# 50_Shot_Relay_V0_0.net
KiCad netlist of a schematic drawn in EAGLE
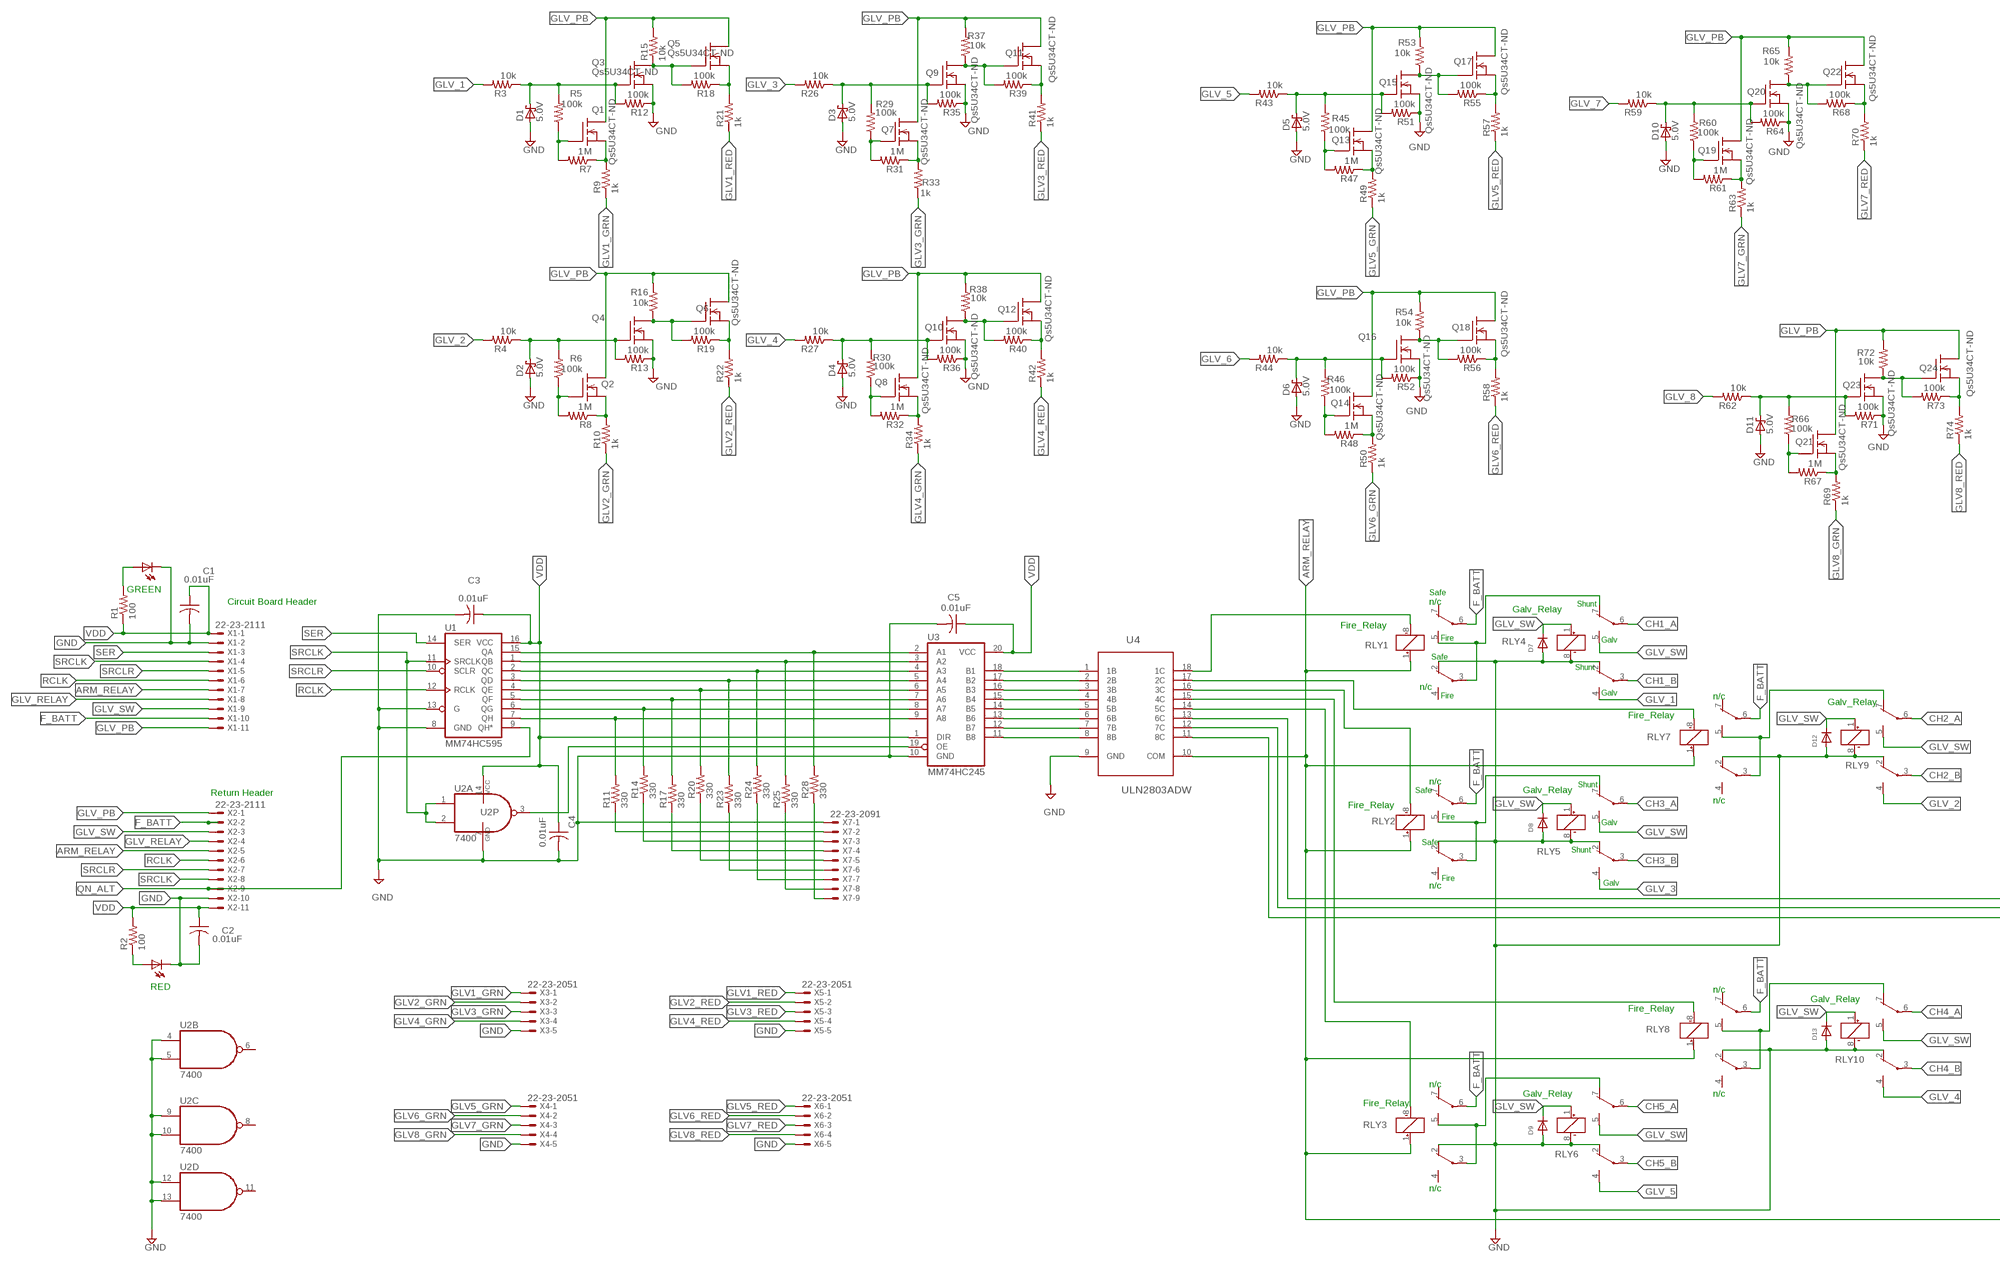
[diagram p0: schematic, sheet 1, part 1 of 2]
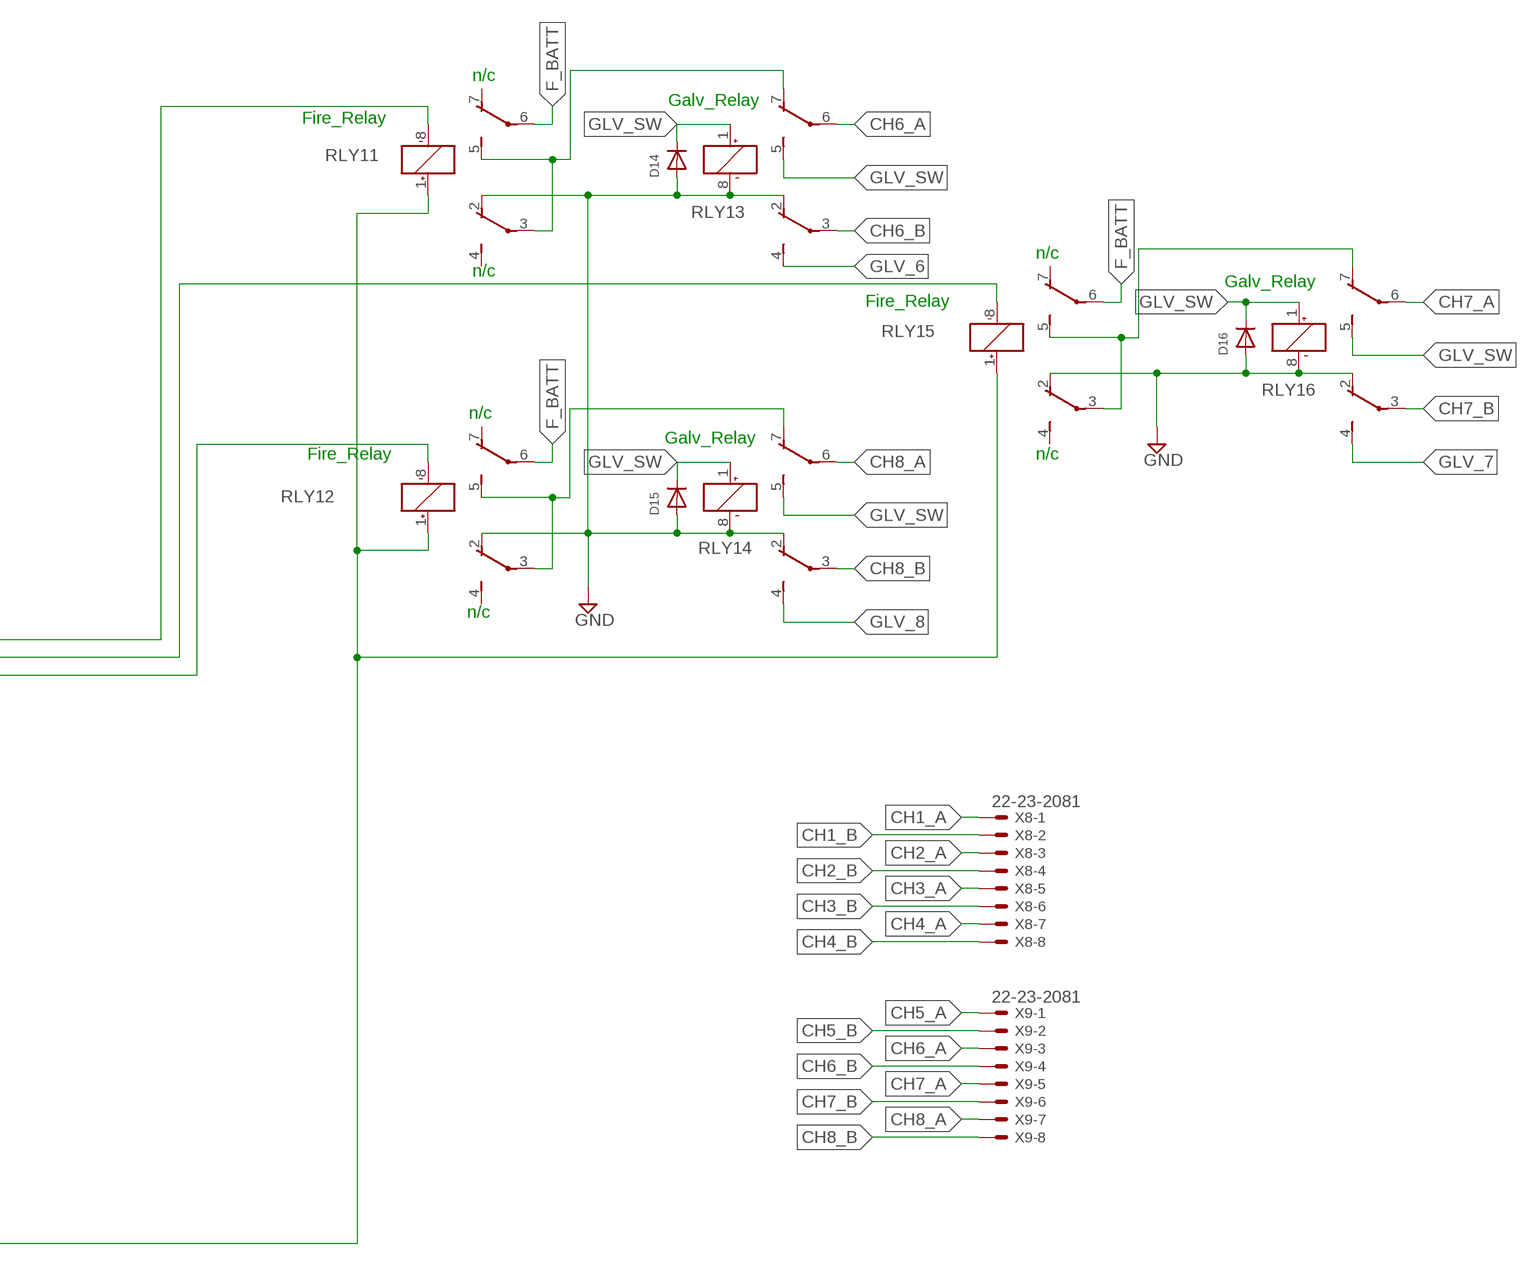
[diagram p1: schematic, sheet 1, part 2 of 2]

(export (version "E")
  (design (tool "Eeschema 10.0.6"))
  (components
    (comp (ref "C1")
      (value "0.01uF")
      (footprint "eagle-import:C0805")
      (fields (field (name "MPN") "VY2103M63Y5US63V7"))
      (libsource (lib "eagle-import") (part "C-USC0805"))
    )
    (comp (ref "C2")
      (value "0.01uF")
      (footprint "eagle-import:C0805")
      (fields (field (name "MPN") "VY2103M63Y5US63V7"))
      (libsource (lib "eagle-import") (part "C-USC0805"))
    )
    (comp (ref "C3")
      (value "0.01uF")
      (footprint "eagle-import:C0805")
      (libsource (lib "eagle-import") (part "C-USC0805"))
    )
    (comp (ref "C4")
      (value "0.01uF")
      (footprint "eagle-import:C0805")
      (libsource (lib "eagle-import") (part "C-USC0805"))
    )
    (comp (ref "C5")
      (value "0.01uF")
      (footprint "eagle-import:C0805")
      (libsource (lib "eagle-import") (part "C-USC0805"))
    )
    (comp (ref "D1")
      (value "5.0V")
      (footprint "eagle-import:SOT23")
      (libsource (lib "eagle-import") (part "568-6471-1-ND_ZENER_5.0V"))
    )
    (comp (ref "D2")
      (value "5.0V")
      (footprint "eagle-import:SOT23")
      (libsource (lib "eagle-import") (part "568-6471-1-ND_ZENER_5.0V"))
    )
    (comp (ref "D3")
      (value "5.0V")
      (footprint "eagle-import:SOT23")
      (libsource (lib "eagle-import") (part "568-6471-1-ND_ZENER_5.0V"))
    )
    (comp (ref "D4")
      (value "5.0V")
      (footprint "eagle-import:SOT23")
      (libsource (lib "eagle-import") (part "568-6471-1-ND_ZENER_5.0V"))
    )
    (comp (ref "D5")
      (value "5.0V")
      (footprint "eagle-import:SOT23")
      (libsource (lib "eagle-import") (part "568-6471-1-ND_ZENER_5.0V"))
    )
    (comp (ref "D6")
      (value "5.0V")
      (footprint "eagle-import:SOT23")
      (libsource (lib "eagle-import") (part "568-6471-1-ND_ZENER_5.0V"))
    )
    (comp (ref "D7")
      (value "SA2M-E3/5ATGICT-ND")
      (footprint "eagle-import:DO214AC")
      (libsource (lib "eagle-import") (part "DIODE_SA2M-E3/5ATGICT-ND"))
    )
    (comp (ref "D8")
      (value "SA2M-E3/5ATGICT-ND")
      (footprint "eagle-import:DO214AC")
      (libsource (lib "eagle-import") (part "DIODE_SA2M-E3/5ATGICT-ND"))
    )
    (comp (ref "D9")
      (value "SA2M-E3/5ATGICT-ND")
      (footprint "eagle-import:DO214AC")
      (libsource (lib "eagle-import") (part "DIODE_SA2M-E3/5ATGICT-ND"))
    )
    (comp (ref "D10")
      (value "5.0V")
      (footprint "eagle-import:SOT23")
      (libsource (lib "eagle-import") (part "568-6471-1-ND_ZENER_5.0V"))
    )
    (comp (ref "D11")
      (value "5.0V")
      (footprint "eagle-import:SOT23")
      (libsource (lib "eagle-import") (part "568-6471-1-ND_ZENER_5.0V"))
    )
    (comp (ref "D12")
      (value "SA2M-E3/5ATGICT-ND")
      (footprint "eagle-import:DO214AC")
      (libsource (lib "eagle-import") (part "DIODE_SA2M-E3/5ATGICT-ND"))
    )
    (comp (ref "D13")
      (value "SA2M-E3/5ATGICT-ND")
      (footprint "eagle-import:DO214AC")
      (libsource (lib "eagle-import") (part "DIODE_SA2M-E3/5ATGICT-ND"))
    )
    (comp (ref "D14")
      (value "SA2M-E3/5ATGICT-ND")
      (footprint "eagle-import:DO214AC")
      (libsource (lib "eagle-import") (part "DIODE_SA2M-E3/5ATGICT-ND"))
    )
    (comp (ref "D15")
      (value "SA2M-E3/5ATGICT-ND")
      (footprint "eagle-import:DO214AC")
      (libsource (lib "eagle-import") (part "DIODE_SA2M-E3/5ATGICT-ND"))
    )
    (comp (ref "D16")
      (value "SA2M-E3/5ATGICT-ND")
      (footprint "eagle-import:DO214AC")
      (libsource (lib "eagle-import") (part "DIODE_SA2M-E3/5ATGICT-ND"))
    )
    (comp (ref "LED1")
      (value "LEDCHIP-LED0805")
      (footprint "eagle-import:CHIP-LED0805")
      (libsource (lib "eagle-import") (part "LEDCHIP-LED0805"))
    )
    (comp (ref "LED2")
      (value "LEDCHIP-LED0805")
      (footprint "eagle-import:CHIP-LED0805")
      (libsource (lib "eagle-import") (part "LEDCHIP-LED0805"))
    )
    (comp (ref "Q1")
      (value "Qs5U34CT-ND")
      (footprint "eagle-import:SOT23-5L")
      (libsource (lib "eagle-import") (part "QS5U34CT-ND_MOSFET_N_CHANNEL"))
    )
    (comp (ref "Q2")
      (value "Qs5U34CT-ND")
      (footprint "eagle-import:SOT23-5L")
      (libsource (lib "eagle-import") (part "QS5U34CT-ND_MOSFET_N_CHANNEL"))
    )
    (comp (ref "Q3")
      (value "Qs5U34CT-ND")
      (footprint "eagle-import:SOT23-5L")
      (libsource (lib "eagle-import") (part "QS5U34CT-ND_MOSFET_N_CHANNEL"))
    )
    (comp (ref "Q4")
      (value "Qs5U34CT-ND")
      (footprint "eagle-import:SOT23-5L")
      (libsource (lib "eagle-import") (part "QS5U34CT-ND_MOSFET_N_CHANNEL"))
    )
    (comp (ref "Q5")
      (value "Qs5U34CT-ND")
      (footprint "eagle-import:SOT23-5L")
      (libsource (lib "eagle-import") (part "QS5U34CT-ND_MOSFET_N_CHANNEL"))
    )
    (comp (ref "Q6")
      (value "Qs5U34CT-ND")
      (footprint "eagle-import:SOT23-5L")
      (libsource (lib "eagle-import") (part "QS5U34CT-ND_MOSFET_N_CHANNEL"))
    )
    (comp (ref "Q7")
      (value "Qs5U34CT-ND")
      (footprint "eagle-import:SOT23-5L")
      (libsource (lib "eagle-import") (part "QS5U34CT-ND_MOSFET_N_CHANNEL"))
    )
    (comp (ref "Q8")
      (value "Qs5U34CT-ND")
      (footprint "eagle-import:SOT23-5L")
      (libsource (lib "eagle-import") (part "QS5U34CT-ND_MOSFET_N_CHANNEL"))
    )
    (comp (ref "Q9")
      (value "Qs5U34CT-ND")
      (footprint "eagle-import:SOT23-5L")
      (libsource (lib "eagle-import") (part "QS5U34CT-ND_MOSFET_N_CHANNEL"))
    )
    (comp (ref "Q10")
      (value "Qs5U34CT-ND")
      (footprint "eagle-import:SOT23-5L")
      (libsource (lib "eagle-import") (part "QS5U34CT-ND_MOSFET_N_CHANNEL"))
    )
    (comp (ref "Q11")
      (value "Qs5U34CT-ND")
      (footprint "eagle-import:SOT23-5L")
      (libsource (lib "eagle-import") (part "QS5U34CT-ND_MOSFET_N_CHANNEL"))
    )
    (comp (ref "Q12")
      (value "Qs5U34CT-ND")
      (footprint "eagle-import:SOT23-5L")
      (libsource (lib "eagle-import") (part "QS5U34CT-ND_MOSFET_N_CHANNEL"))
    )
    (comp (ref "Q13")
      (value "Qs5U34CT-ND")
      (footprint "eagle-import:SOT23-5L")
      (libsource (lib "eagle-import") (part "QS5U34CT-ND_MOSFET_N_CHANNEL"))
    )
    (comp (ref "Q14")
      (value "Qs5U34CT-ND")
      (footprint "eagle-import:SOT23-5L")
      (libsource (lib "eagle-import") (part "QS5U34CT-ND_MOSFET_N_CHANNEL"))
    )
    (comp (ref "Q15")
      (value "Qs5U34CT-ND")
      (footprint "eagle-import:SOT23-5L")
      (libsource (lib "eagle-import") (part "QS5U34CT-ND_MOSFET_N_CHANNEL"))
    )
    (comp (ref "Q16")
      (value "Qs5U34CT-ND")
      (footprint "eagle-import:SOT23-5L")
      (libsource (lib "eagle-import") (part "QS5U34CT-ND_MOSFET_N_CHANNEL"))
    )
    (comp (ref "Q17")
      (value "Qs5U34CT-ND")
      (footprint "eagle-import:SOT23-5L")
      (libsource (lib "eagle-import") (part "QS5U34CT-ND_MOSFET_N_CHANNEL"))
    )
    (comp (ref "Q18")
      (value "Qs5U34CT-ND")
      (footprint "eagle-import:SOT23-5L")
      (libsource (lib "eagle-import") (part "QS5U34CT-ND_MOSFET_N_CHANNEL"))
    )
    (comp (ref "Q19")
      (value "Qs5U34CT-ND")
      (footprint "eagle-import:SOT23-5L")
      (libsource (lib "eagle-import") (part "QS5U34CT-ND_MOSFET_N_CHANNEL"))
    )
    (comp (ref "Q20")
      (value "Qs5U34CT-ND")
      (footprint "eagle-import:SOT23-5L")
      (libsource (lib "eagle-import") (part "QS5U34CT-ND_MOSFET_N_CHANNEL"))
    )
    (comp (ref "Q21")
      (value "Qs5U34CT-ND")
      (footprint "eagle-import:SOT23-5L")
      (libsource (lib "eagle-import") (part "QS5U34CT-ND_MOSFET_N_CHANNEL"))
    )
    (comp (ref "Q22")
      (value "Qs5U34CT-ND")
      (footprint "eagle-import:SOT23-5L")
      (libsource (lib "eagle-import") (part "QS5U34CT-ND_MOSFET_N_CHANNEL"))
    )
    (comp (ref "Q23")
      (value "Qs5U34CT-ND")
      (footprint "eagle-import:SOT23-5L")
      (libsource (lib "eagle-import") (part "QS5U34CT-ND_MOSFET_N_CHANNEL"))
    )
    (comp (ref "Q24")
      (value "Qs5U34CT-ND")
      (footprint "eagle-import:SOT23-5L")
      (libsource (lib "eagle-import") (part "QS5U34CT-ND_MOSFET_N_CHANNEL"))
    )
    (comp (ref "R1")
      (value "100")
      (footprint "eagle-import:M0805")
      (libsource (lib "eagle-import") (part "R-US_M0805"))
    )
    (comp (ref "R2")
      (value "100")
      (footprint "eagle-import:M0805")
      (libsource (lib "eagle-import") (part "R-US_M0805"))
    )
    (comp (ref "R3")
      (value "10k")
      (footprint "eagle-import:M0805")
      (libsource (lib "eagle-import") (part "R-US_M0805"))
    )
    (comp (ref "R4")
      (value "10k")
      (footprint "eagle-import:M0805")
      (libsource (lib "eagle-import") (part "R-US_M0805"))
    )
    (comp (ref "R5")
      (value "100k")
      (footprint "eagle-import:M0805")
      (libsource (lib "eagle-import") (part "R-US_M0805"))
    )
    (comp (ref "R6")
      (value "100k")
      (footprint "eagle-import:M0805")
      (libsource (lib "eagle-import") (part "R-US_M0805"))
    )
    (comp (ref "R7")
      (value "1M")
      (footprint "eagle-import:M0805")
      (libsource (lib "eagle-import") (part "R-US_M0805"))
    )
    (comp (ref "R8")
      (value "1M")
      (footprint "eagle-import:M0805")
      (libsource (lib "eagle-import") (part "R-US_M0805"))
    )
    (comp (ref "R9")
      (value "1k")
      (footprint "eagle-import:M0805")
      (libsource (lib "eagle-import") (part "R-US_M0805"))
    )
    (comp (ref "R10")
      (value "1k")
      (footprint "eagle-import:M0805")
      (libsource (lib "eagle-import") (part "R-US_M0805"))
    )
    (comp (ref "R11")
      (value "330")
      (footprint "eagle-import:M0805")
      (libsource (lib "eagle-import") (part "R-US_M0805"))
    )
    (comp (ref "R12")
      (value "100k")
      (footprint "eagle-import:M0805")
      (libsource (lib "eagle-import") (part "R-US_M0805"))
    )
    (comp (ref "R13")
      (value "100k")
      (footprint "eagle-import:M0805")
      (libsource (lib "eagle-import") (part "R-US_M0805"))
    )
    (comp (ref "R14")
      (value "330")
      (footprint "eagle-import:M0805")
      (libsource (lib "eagle-import") (part "R-US_M0805"))
    )
    (comp (ref "R15")
      (value "10k")
      (footprint "eagle-import:M0805")
      (libsource (lib "eagle-import") (part "R-US_M0805"))
    )
    (comp (ref "R16")
      (value "10k")
      (footprint "eagle-import:M0805")
      (libsource (lib "eagle-import") (part "R-US_M0805"))
    )
    (comp (ref "R17")
      (value "330")
      (footprint "eagle-import:M0805")
      (libsource (lib "eagle-import") (part "R-US_M0805"))
    )
    (comp (ref "R18")
      (value "100k")
      (footprint "eagle-import:M0805")
      (libsource (lib "eagle-import") (part "R-US_M0805"))
    )
    (comp (ref "R19")
      (value "100k")
      (footprint "eagle-import:M0805")
      (libsource (lib "eagle-import") (part "R-US_M0805"))
    )
    (comp (ref "R20")
      (value "330")
      (footprint "eagle-import:M0805")
      (libsource (lib "eagle-import") (part "R-US_M0805"))
    )
    (comp (ref "R21")
      (value "1k")
      (footprint "eagle-import:M0805")
      (libsource (lib "eagle-import") (part "R-US_M0805"))
    )
    (comp (ref "R22")
      (value "1k")
      (footprint "eagle-import:M0805")
      (libsource (lib "eagle-import") (part "R-US_M0805"))
    )
    (comp (ref "R23")
      (value "330")
      (footprint "eagle-import:M0805")
      (libsource (lib "eagle-import") (part "R-US_M0805"))
    )
    (comp (ref "R24")
      (value "330")
      (footprint "eagle-import:M0805")
      (libsource (lib "eagle-import") (part "R-US_M0805"))
    )
    (comp (ref "R25")
      (value "330")
      (footprint "eagle-import:M0805")
      (libsource (lib "eagle-import") (part "R-US_M0805"))
    )
    (comp (ref "R26")
      (value "10k")
      (footprint "eagle-import:M0805")
      (libsource (lib "eagle-import") (part "R-US_M0805"))
    )
    (comp (ref "R27")
      (value "10k")
      (footprint "eagle-import:M0805")
      (libsource (lib "eagle-import") (part "R-US_M0805"))
    )
    (comp (ref "R28")
      (value "330")
      (footprint "eagle-import:M0805")
      (libsource (lib "eagle-import") (part "R-US_M0805"))
    )
    (comp (ref "R29")
      (value "100k")
      (footprint "eagle-import:M0805")
      (libsource (lib "eagle-import") (part "R-US_M0805"))
    )
    (comp (ref "R30")
      (value "100k")
      (footprint "eagle-import:M0805")
      (libsource (lib "eagle-import") (part "R-US_M0805"))
    )
    (comp (ref "R31")
      (value "1M")
      (footprint "eagle-import:M0805")
      (libsource (lib "eagle-import") (part "R-US_M0805"))
    )
    (comp (ref "R32")
      (value "1M")
      (footprint "eagle-import:M0805")
      (libsource (lib "eagle-import") (part "R-US_M0805"))
    )
    (comp (ref "R33")
      (value "1k")
      (footprint "eagle-import:M0805")
      (libsource (lib "eagle-import") (part "R-US_M0805"))
    )
    (comp (ref "R34")
      (value "1k")
      (footprint "eagle-import:M0805")
      (libsource (lib "eagle-import") (part "R-US_M0805"))
    )
    (comp (ref "R35")
      (value "100k")
      (footprint "eagle-import:M0805")
      (libsource (lib "eagle-import") (part "R-US_M0805"))
    )
    (comp (ref "R36")
      (value "100k")
      (footprint "eagle-import:M0805")
      (libsource (lib "eagle-import") (part "R-US_M0805"))
    )
    (comp (ref "R37")
      (value "10k")
      (footprint "eagle-import:M0805")
      (libsource (lib "eagle-import") (part "R-US_M0805"))
    )
    (comp (ref "R38")
      (value "10k")
      (footprint "eagle-import:M0805")
      (libsource (lib "eagle-import") (part "R-US_M0805"))
    )
    (comp (ref "R39")
      (value "100k")
      (footprint "eagle-import:M0805")
      (libsource (lib "eagle-import") (part "R-US_M0805"))
    )
    (comp (ref "R40")
      (value "100k")
      (footprint "eagle-import:M0805")
      (libsource (lib "eagle-import") (part "R-US_M0805"))
    )
    (comp (ref "R41")
      (value "1k")
      (footprint "eagle-import:M0805")
      (libsource (lib "eagle-import") (part "R-US_M0805"))
    )
    (comp (ref "R42")
      (value "1k")
      (footprint "eagle-import:M0805")
      (libsource (lib "eagle-import") (part "R-US_M0805"))
    )
    (comp (ref "R43")
      (value "10k")
      (footprint "eagle-import:M0805")
      (libsource (lib "eagle-import") (part "R-US_M0805"))
    )
    (comp (ref "R44")
      (value "10k")
      (footprint "eagle-import:M0805")
      (libsource (lib "eagle-import") (part "R-US_M0805"))
    )
    (comp (ref "R45")
      (value "100k")
      (footprint "eagle-import:M0805")
      (libsource (lib "eagle-import") (part "R-US_M0805"))
    )
    (comp (ref "R46")
      (value "100k")
      (footprint "eagle-import:M0805")
      (libsource (lib "eagle-import") (part "R-US_M0805"))
    )
    (comp (ref "R47")
      (value "1M")
      (footprint "eagle-import:M0805")
      (libsource (lib "eagle-import") (part "R-US_M0805"))
    )
    (comp (ref "R48")
      (value "1M")
      (footprint "eagle-import:M0805")
      (libsource (lib "eagle-import") (part "R-US_M0805"))
    )
    (comp (ref "R49")
      (value "1k")
      (footprint "eagle-import:M0805")
      (libsource (lib "eagle-import") (part "R-US_M0805"))
    )
    (comp (ref "R50")
      (value "1k")
      (footprint "eagle-import:M0805")
      (libsource (lib "eagle-import") (part "R-US_M0805"))
    )
    (comp (ref "R51")
      (value "100k")
      (footprint "eagle-import:M0805")
      (libsource (lib "eagle-import") (part "R-US_M0805"))
    )
    (comp (ref "R52")
      (value "100k")
      (footprint "eagle-import:M0805")
      (libsource (lib "eagle-import") (part "R-US_M0805"))
    )
    (comp (ref "R53")
      (value "10k")
      (footprint "eagle-import:M0805")
      (libsource (lib "eagle-import") (part "R-US_M0805"))
    )
    (comp (ref "R54")
      (value "10k")
      (footprint "eagle-import:M0805")
      (libsource (lib "eagle-import") (part "R-US_M0805"))
    )
    (comp (ref "R55")
      (value "100k")
      (footprint "eagle-import:M0805")
      (libsource (lib "eagle-import") (part "R-US_M0805"))
    )
    (comp (ref "R56")
      (value "100k")
      (footprint "eagle-import:M0805")
      (libsource (lib "eagle-import") (part "R-US_M0805"))
    )
    (comp (ref "R57")
      (value "1k")
      (footprint "eagle-import:M0805")
      (libsource (lib "eagle-import") (part "R-US_M0805"))
    )
    (comp (ref "R58")
      (value "1k")
      (footprint "eagle-import:M0805")
      (libsource (lib "eagle-import") (part "R-US_M0805"))
    )
    (comp (ref "R59")
      (value "10k")
      (footprint "eagle-import:M0805")
      (libsource (lib "eagle-import") (part "R-US_M0805"))
    )
    (comp (ref "R60")
      (value "100k")
      (footprint "eagle-import:M0805")
      (libsource (lib "eagle-import") (part "R-US_M0805"))
    )
    (comp (ref "R61")
      (value "1M")
      (footprint "eagle-import:M0805")
      (libsource (lib "eagle-import") (part "R-US_M0805"))
    )
    (comp (ref "R62")
      (value "10k")
      (footprint "eagle-import:M0805")
      (libsource (lib "eagle-import") (part "R-US_M0805"))
    )
    (comp (ref "R63")
      (value "1k")
      (footprint "eagle-import:M0805")
      (libsource (lib "eagle-import") (part "R-US_M0805"))
    )
    (comp (ref "R64")
      (value "100k")
      (footprint "eagle-import:M0805")
      (libsource (lib "eagle-import") (part "R-US_M0805"))
    )
    (comp (ref "R65")
      (value "10k")
      (footprint "eagle-import:M0805")
      (libsource (lib "eagle-import") (part "R-US_M0805"))
    )
    (comp (ref "R66")
      (value "100k")
      (footprint "eagle-import:M0805")
      (libsource (lib "eagle-import") (part "R-US_M0805"))
    )
    (comp (ref "R67")
      (value "1M")
      (footprint "eagle-import:M0805")
      (libsource (lib "eagle-import") (part "R-US_M0805"))
    )
    (comp (ref "R68")
      (value "100k")
      (footprint "eagle-import:M0805")
      (libsource (lib "eagle-import") (part "R-US_M0805"))
    )
    (comp (ref "R69")
      (value "1k")
      (footprint "eagle-import:M0805")
      (libsource (lib "eagle-import") (part "R-US_M0805"))
    )
    (comp (ref "R70")
      (value "1k")
      (footprint "eagle-import:M0805")
      (libsource (lib "eagle-import") (part "R-US_M0805"))
    )
    (comp (ref "R71")
      (value "100k")
      (footprint "eagle-import:M0805")
      (libsource (lib "eagle-import") (part "R-US_M0805"))
    )
    (comp (ref "R72")
      (value "10k")
      (footprint "eagle-import:M0805")
      (libsource (lib "eagle-import") (part "R-US_M0805"))
    )
    (comp (ref "R73")
      (value "100k")
      (footprint "eagle-import:M0805")
      (libsource (lib "eagle-import") (part "R-US_M0805"))
    )
    (comp (ref "R74")
      (value "1k")
      (footprint "eagle-import:M0805")
      (libsource (lib "eagle-import") (part "R-US_M0805"))
    )
    (comp (ref "RLY1")
      (value "OMRON")
      (footprint "eagle-import:OMRONG6S")
      (fields (field (name "OC_NEWARK") "unknown"))
      (libsource (lib "eagle-import") (part "OMRON"))
    )
    (comp (ref "RLY2")
      (value "OMRON")
      (footprint "eagle-import:OMRONG6S")
      (fields (field (name "OC_NEWARK") "unknown"))
      (libsource (lib "eagle-import") (part "OMRON"))
    )
    (comp (ref "RLY3")
      (value "OMRON")
      (footprint "eagle-import:OMRONG6S")
      (fields (field (name "OC_NEWARK") "unknown"))
      (libsource (lib "eagle-import") (part "OMRON"))
    )
    (comp (ref "RLY4")
      (value "OMRON")
      (footprint "eagle-import:OMRONG6S")
      (fields (field (name "OC_NEWARK") "unknown"))
      (libsource (lib "eagle-import") (part "OMRON"))
    )
    (comp (ref "RLY5")
      (value "OMRON")
      (footprint "eagle-import:OMRONG6S")
      (fields (field (name "OC_NEWARK") "unknown"))
      (libsource (lib "eagle-import") (part "OMRON"))
    )
    (comp (ref "RLY6")
      (value "OMRON")
      (footprint "eagle-import:OMRONG6S")
      (fields (field (name "OC_NEWARK") "unknown"))
      (libsource (lib "eagle-import") (part "OMRON"))
    )
    (comp (ref "RLY7")
      (value "OMRON")
      (footprint "eagle-import:OMRONG6S")
      (fields (field (name "OC_NEWARK") "unknown"))
      (libsource (lib "eagle-import") (part "OMRON"))
    )
    (comp (ref "RLY8")
      (value "OMRON")
      (footprint "eagle-import:OMRONG6S")
      (fields (field (name "OC_NEWARK") "unknown"))
      (libsource (lib "eagle-import") (part "OMRON"))
    )
    (comp (ref "RLY9")
      (value "OMRON")
      (footprint "eagle-import:OMRONG6S")
      (fields (field (name "OC_NEWARK") "unknown"))
      (libsource (lib "eagle-import") (part "OMRON"))
    )
    (comp (ref "RLY10")
      (value "OMRON")
      (footprint "eagle-import:OMRONG6S")
      (fields (field (name "OC_NEWARK") "unknown"))
      (libsource (lib "eagle-import") (part "OMRON"))
    )
    (comp (ref "RLY11")
      (value "OMRON")
      (footprint "eagle-import:OMRONG6S")
      (fields (field (name "OC_NEWARK") "unknown"))
      (libsource (lib "eagle-import") (part "OMRON"))
    )
    (comp (ref "RLY12")
      (value "OMRON")
      (footprint "eagle-import:OMRONG6S")
      (fields (field (name "OC_NEWARK") "unknown"))
      (libsource (lib "eagle-import") (part "OMRON"))
    )
    (comp (ref "RLY13")
      (value "OMRON")
      (footprint "eagle-import:OMRONG6S")
      (fields (field (name "OC_NEWARK") "unknown"))
      (libsource (lib "eagle-import") (part "OMRON"))
    )
    (comp (ref "RLY14")
      (value "OMRON")
      (footprint "eagle-import:OMRONG6S")
      (fields (field (name "OC_NEWARK") "unknown"))
      (libsource (lib "eagle-import") (part "OMRON"))
    )
    (comp (ref "RLY15")
      (value "OMRON")
      (footprint "eagle-import:OMRONG6S")
      (fields (field (name "OC_NEWARK") "unknown"))
      (libsource (lib "eagle-import") (part "OMRON"))
    )
    (comp (ref "RLY16")
      (value "OMRON")
      (footprint "eagle-import:OMRONG6S")
      (fields (field (name "OC_NEWARK") "unknown"))
      (libsource (lib "eagle-import") (part "OMRON"))
    )
    (comp (ref "U1")
      (value "MM74HC595")
      (footprint "eagle-import:TSSOP16")
      (libsource (lib "eagle-import") (part "MM74HC595"))
    )
    (comp (ref "U2")
      (value "7400")
      (footprint "eagle-import:TSSOP14")
      (fields (field (name "OC_NEWARK") "unknown"))
      (libsource (lib "eagle-import") (part "7400"))
    )
    (comp (ref "U3")
      (value "MM74HC245")
      (footprint "eagle-import:TSSOP20")
      (libsource (lib "eagle-import") (part "MM74HC245"))
    )
    (comp (ref "U4")
      (value "ULN2803ADW")
      (footprint "eagle-import:SOIC127P1030X265-18N")
      (fields (field (name "MF") "TEXAS INSTRUMENTS"))
      (libsource (lib "eagle-import") (part "ULN2803ADW"))
    )
    (comp (ref "X1")
      (value "22-23-2111")
      (footprint "eagle-import:22-23-2111")
      (fields (field (name "MF") "MOLEX") (field (name "OC_NEWARK") "unknown"))
      (libsource (lib "eagle-import") (part "22-23-2111"))
    )
    (comp (ref "X2")
      (value "22-23-2111")
      (footprint "eagle-import:22-23-2111")
      (fields (field (name "MF") "MOLEX") (field (name "OC_NEWARK") "unknown"))
      (libsource (lib "eagle-import") (part "22-23-2111"))
    )
    (comp (ref "X3")
      (value "22-23-2051")
      (footprint "eagle-import:22-23-2051")
      (fields (field (name "MF") "MOLEX"))
      (libsource (lib "eagle-import") (part "22-23-2051"))
    )
    (comp (ref "X4")
      (value "22-23-2051")
      (footprint "eagle-import:22-23-2051")
      (fields (field (name "MF") "MOLEX"))
      (libsource (lib "eagle-import") (part "22-23-2051"))
    )
    (comp (ref "X5")
      (value "22-23-2051")
      (footprint "eagle-import:22-23-2051")
      (fields (field (name "MF") "MOLEX"))
      (libsource (lib "eagle-import") (part "22-23-2051"))
    )
    (comp (ref "X6")
      (value "22-23-2051")
      (footprint "eagle-import:22-23-2051")
      (fields (field (name "MF") "MOLEX"))
      (libsource (lib "eagle-import") (part "22-23-2051"))
    )
    (comp (ref "X7")
      (value "22-23-2091")
      (footprint "eagle-import:22-23-2091")
      (fields (field (name "MF") "MOLEX"))
      (libsource (lib "eagle-import") (part "22-23-2091"))
    )
    (comp (ref "X8")
      (value "22-23-2081")
      (footprint "eagle-import:22-23-2081")
      (fields (field (name "MF") "MOLEX"))
      (libsource (lib "eagle-import") (part "22-23-2081"))
    )
    (comp (ref "X9")
      (value "22-23-2081")
      (footprint "eagle-import:22-23-2081")
      (fields (field (name "MF") "MOLEX"))
      (libsource (lib "eagle-import") (part "22-23-2081"))
    )
  )
  (nets
    (net (code "1") (name "ARM_RELAY") (class "Default")
      (node (ref "RLY1") (pin "1") (pinfunction "+_1") (pintype "passive"))
      (node (ref "RLY11") (pin "1") (pinfunction "+_1") (pintype "passive"))
      (node (ref "RLY12") (pin "1") (pinfunction "+_1") (pintype "passive"))
      (node (ref "RLY15") (pin "1") (pinfunction "+_1") (pintype "passive"))
      (node (ref "RLY2") (pin "1") (pinfunction "+_1") (pintype "passive"))
      (node (ref "RLY3") (pin "1") (pinfunction "+_1") (pintype "passive"))
      (node (ref "RLY7") (pin "1") (pinfunction "+_1") (pintype "passive"))
      (node (ref "RLY8") (pin "1") (pinfunction "+_1") (pintype "passive"))
      (node (ref "U4") (pin "10") (pinfunction "COM_10") (pintype "tri_state"))
      (node (ref "X1") (pin "7") (pinfunction "S_7") (pintype "passive"))
      (node (ref "X2") (pin "5") (pinfunction "S_5") (pintype "passive"))
    )
    (net (code "2") (name "CH1_A") (class "Default")
      (node (ref "RLY4") (pin "6") (pinfunction "P_6") (pintype "passive"))
      (node (ref "X8") (pin "1") (pinfunction "S_1") (pintype "passive"))
    )
    (net (code "3") (name "CH1_B") (class "Default")
      (node (ref "RLY4") (pin "3") (pinfunction "P_3") (pintype "passive"))
      (node (ref "X8") (pin "2") (pinfunction "S_2") (pintype "passive"))
    )
    (net (code "4") (name "CH2_A") (class "Default")
      (node (ref "RLY9") (pin "6") (pinfunction "P_6") (pintype "passive"))
      (node (ref "X8") (pin "3") (pinfunction "S_3") (pintype "passive"))
    )
    (net (code "5") (name "CH2_B") (class "Default")
      (node (ref "RLY9") (pin "3") (pinfunction "P_3") (pintype "passive"))
      (node (ref "X8") (pin "4") (pinfunction "S_4") (pintype "passive"))
    )
    (net (code "6") (name "CH3_A") (class "Default")
      (node (ref "RLY5") (pin "6") (pinfunction "P_6") (pintype "passive"))
      (node (ref "X8") (pin "5") (pinfunction "S_5") (pintype "passive"))
    )
    (net (code "7") (name "CH3_B") (class "Default")
      (node (ref "RLY5") (pin "3") (pinfunction "P_3") (pintype "passive"))
      (node (ref "X8") (pin "6") (pinfunction "S_6") (pintype "passive"))
    )
    (net (code "8") (name "CH4_A") (class "Default")
      (node (ref "RLY10") (pin "6") (pinfunction "P_6") (pintype "passive"))
      (node (ref "X8") (pin "7") (pinfunction "S_7") (pintype "passive"))
    )
    (net (code "9") (name "CH4_B") (class "Default")
      (node (ref "RLY10") (pin "3") (pinfunction "P_3") (pintype "passive"))
      (node (ref "X8") (pin "8") (pinfunction "S_8") (pintype "passive"))
    )
    (net (code "10") (name "CH5_A") (class "Default")
      (node (ref "RLY6") (pin "6") (pinfunction "P_6") (pintype "passive"))
      (node (ref "X9") (pin "1") (pinfunction "S_1") (pintype "passive"))
    )
    (net (code "11") (name "CH5_B") (class "Default")
      (node (ref "RLY6") (pin "3") (pinfunction "P_3") (pintype "passive"))
      (node (ref "X9") (pin "2") (pinfunction "S_2") (pintype "passive"))
    )
    (net (code "12") (name "CH6_A") (class "Default")
      (node (ref "RLY13") (pin "6") (pinfunction "P_6") (pintype "passive"))
      (node (ref "X9") (pin "3") (pinfunction "S_3") (pintype "passive"))
    )
    (net (code "13") (name "CH6_B") (class "Default")
      (node (ref "RLY13") (pin "3") (pinfunction "P_3") (pintype "passive"))
      (node (ref "X9") (pin "4") (pinfunction "S_4") (pintype "passive"))
    )
    (net (code "14") (name "CH7_A") (class "Default")
      (node (ref "RLY16") (pin "6") (pinfunction "P_6") (pintype "passive"))
      (node (ref "X9") (pin "5") (pinfunction "S_5") (pintype "passive"))
    )
    (net (code "15") (name "CH7_B") (class "Default")
      (node (ref "RLY16") (pin "3") (pinfunction "P_3") (pintype "passive"))
      (node (ref "X9") (pin "6") (pinfunction "S_6") (pintype "passive"))
    )
    (net (code "16") (name "CH8_A") (class "Default")
      (node (ref "RLY14") (pin "6") (pinfunction "P_6") (pintype "passive"))
      (node (ref "X9") (pin "7") (pinfunction "S_7") (pintype "passive"))
    )
    (net (code "17") (name "CH8_B") (class "Default")
      (node (ref "RLY14") (pin "3") (pinfunction "P_3") (pintype "passive"))
      (node (ref "X9") (pin "8") (pinfunction "S_8") (pintype "passive"))
    )
    (net (code "18") (name "F_BATT") (class "Default")
      (node (ref "RLY1") (pin "6") (pinfunction "P_6") (pintype "passive"))
      (node (ref "RLY11") (pin "6") (pinfunction "P_6") (pintype "passive"))
      (node (ref "RLY12") (pin "6") (pinfunction "P_6") (pintype "passive"))
      (node (ref "RLY15") (pin "6") (pinfunction "P_6") (pintype "passive"))
      (node (ref "RLY2") (pin "6") (pinfunction "P_6") (pintype "passive"))
      (node (ref "RLY3") (pin "6") (pinfunction "P_6") (pintype "passive"))
      (node (ref "RLY7") (pin "6") (pinfunction "P_6") (pintype "passive"))
      (node (ref "RLY8") (pin "6") (pinfunction "P_6") (pintype "passive"))
      (node (ref "X1") (pin "10") (pinfunction "S_10") (pintype "passive"))
      (node (ref "X2") (pin "2") (pinfunction "S_2") (pintype "passive"))
    )
    (net (code "19") (name "GLV1_GRN") (class "Default")
      (node (ref "R9") (pin "1") (pinfunction "1_1") (pintype "passive"))
      (node (ref "X3") (pin "1") (pinfunction "S_1") (pintype "passive"))
    )
    (net (code "20") (name "GLV1_RED") (class "Default")
      (node (ref "R21") (pin "1") (pinfunction "1_1") (pintype "passive"))
      (node (ref "X5") (pin "1") (pinfunction "S_1") (pintype "passive"))
    )
    (net (code "21") (name "GLV2_GRN") (class "Default")
      (node (ref "R10") (pin "1") (pinfunction "1_1") (pintype "passive"))
      (node (ref "X3") (pin "2") (pinfunction "S_2") (pintype "passive"))
    )
    (net (code "22") (name "GLV2_RED") (class "Default")
      (node (ref "R22") (pin "1") (pinfunction "1_1") (pintype "passive"))
      (node (ref "X5") (pin "2") (pinfunction "S_2") (pintype "passive"))
    )
    (net (code "23") (name "GLV3_GRN") (class "Default")
      (node (ref "R33") (pin "1") (pinfunction "1_1") (pintype "passive"))
      (node (ref "X3") (pin "3") (pinfunction "S_3") (pintype "passive"))
    )
    (net (code "24") (name "GLV3_RED") (class "Default")
      (node (ref "R41") (pin "1") (pinfunction "1_1") (pintype "passive"))
      (node (ref "X5") (pin "3") (pinfunction "S_3") (pintype "passive"))
    )
    (net (code "25") (name "GLV4_GRN") (class "Default")
      (node (ref "R34") (pin "1") (pinfunction "1_1") (pintype "passive"))
      (node (ref "X3") (pin "4") (pinfunction "S_4") (pintype "passive"))
    )
    (net (code "26") (name "GLV4_RED") (class "Default")
      (node (ref "R42") (pin "1") (pinfunction "1_1") (pintype "passive"))
      (node (ref "X5") (pin "4") (pinfunction "S_4") (pintype "passive"))
    )
    (net (code "27") (name "GLV5_GRN") (class "Default")
      (node (ref "R49") (pin "1") (pinfunction "1_1") (pintype "passive"))
      (node (ref "X4") (pin "1") (pinfunction "S_1") (pintype "passive"))
    )
    (net (code "28") (name "GLV5_RED") (class "Default")
      (node (ref "R57") (pin "1") (pinfunction "1_1") (pintype "passive"))
      (node (ref "X6") (pin "1") (pinfunction "S_1") (pintype "passive"))
    )
    (net (code "29") (name "GLV6_GRN") (class "Default")
      (node (ref "R50") (pin "1") (pinfunction "1_1") (pintype "passive"))
      (node (ref "X4") (pin "2") (pinfunction "S_2") (pintype "passive"))
    )
    (net (code "30") (name "GLV6_RED") (class "Default")
      (node (ref "R58") (pin "1") (pinfunction "1_1") (pintype "passive"))
      (node (ref "X6") (pin "2") (pinfunction "S_2") (pintype "passive"))
    )
    (net (code "31") (name "GLV7_GRN") (class "Default")
      (node (ref "R63") (pin "1") (pinfunction "1_1") (pintype "passive"))
      (node (ref "X4") (pin "3") (pinfunction "S_3") (pintype "passive"))
    )
    (net (code "32") (name "GLV7_RED") (class "Default")
      (node (ref "R70") (pin "1") (pinfunction "1_1") (pintype "passive"))
      (node (ref "X6") (pin "3") (pinfunction "S_3") (pintype "passive"))
    )
    (net (code "33") (name "GLV8_GRN") (class "Default")
      (node (ref "R69") (pin "1") (pinfunction "1_1") (pintype "passive"))
      (node (ref "X4") (pin "4") (pinfunction "S_4") (pintype "passive"))
    )
    (net (code "34") (name "GLV8_RED") (class "Default")
      (node (ref "R74") (pin "1") (pinfunction "1_1") (pintype "passive"))
      (node (ref "X6") (pin "4") (pinfunction "S_4") (pintype "passive"))
    )
    (net (code "35") (name "GLV_1") (class "Default")
      (node (ref "R3") (pin "2") (pinfunction "2_2") (pintype "passive"))
      (node (ref "RLY4") (pin "4") (pinfunction "S_4") (pintype "passive"))
    )
    (net (code "36") (name "GLV_2") (class "Default")
      (node (ref "R4") (pin "2") (pinfunction "2_2") (pintype "passive"))
      (node (ref "RLY9") (pin "4") (pinfunction "S_4") (pintype "passive"))
    )
    (net (code "37") (name "GLV_3") (class "Default")
      (node (ref "R26") (pin "2") (pinfunction "2_2") (pintype "passive"))
      (node (ref "RLY5") (pin "4") (pinfunction "S_4") (pintype "passive"))
    )
    (net (code "38") (name "GLV_4") (class "Default")
      (node (ref "R27") (pin "2") (pinfunction "2_2") (pintype "passive"))
      (node (ref "RLY10") (pin "4") (pinfunction "S_4") (pintype "passive"))
    )
    (net (code "39") (name "GLV_5") (class "Default")
      (node (ref "R43") (pin "2") (pinfunction "2_2") (pintype "passive"))
      (node (ref "RLY6") (pin "4") (pinfunction "S_4") (pintype "passive"))
    )
    (net (code "40") (name "GLV_6") (class "Default")
      (node (ref "R44") (pin "2") (pinfunction "2_2") (pintype "passive"))
      (node (ref "RLY13") (pin "4") (pinfunction "S_4") (pintype "passive"))
    )
    (net (code "41") (name "GLV_7") (class "Default")
      (node (ref "R59") (pin "2") (pinfunction "2_2") (pintype "passive"))
      (node (ref "RLY16") (pin "4") (pinfunction "S_4") (pintype "passive"))
    )
    (net (code "42") (name "GLV_8") (class "Default")
      (node (ref "R62") (pin "2") (pinfunction "2_2") (pintype "passive"))
      (node (ref "RLY14") (pin "4") (pinfunction "S_4") (pintype "passive"))
    )
    (net (code "43") (name "GLV_PB") (class "Default")
      (node (ref "Q1") (pin "5") (pinfunction "D_5") (pintype "passive"))
      (node (ref "Q11") (pin "5") (pinfunction "D_5") (pintype "passive"))
      (node (ref "Q12") (pin "5") (pinfunction "D_5") (pintype "passive"))
      (node (ref "Q13") (pin "5") (pinfunction "D_5") (pintype "passive"))
      (node (ref "Q14") (pin "5") (pinfunction "D_5") (pintype "passive"))
      (node (ref "Q17") (pin "5") (pinfunction "D_5") (pintype "passive"))
      (node (ref "Q18") (pin "5") (pinfunction "D_5") (pintype "passive"))
      (node (ref "Q19") (pin "5") (pinfunction "D_5") (pintype "passive"))
      (node (ref "Q2") (pin "5") (pinfunction "D_5") (pintype "passive"))
      (node (ref "Q21") (pin "5") (pinfunction "D_5") (pintype "passive"))
      (node (ref "Q22") (pin "5") (pinfunction "D_5") (pintype "passive"))
      (node (ref "Q24") (pin "5") (pinfunction "D_5") (pintype "passive"))
      (node (ref "Q5") (pin "5") (pinfunction "D_5") (pintype "passive"))
      (node (ref "Q6") (pin "5") (pinfunction "D_5") (pintype "passive"))
      (node (ref "Q7") (pin "5") (pinfunction "D_5") (pintype "passive"))
      (node (ref "Q8") (pin "5") (pinfunction "D_5") (pintype "passive"))
      (node (ref "R15") (pin "2") (pinfunction "2_2") (pintype "passive"))
      (node (ref "R16") (pin "2") (pinfunction "2_2") (pintype "passive"))
      (node (ref "R37") (pin "2") (pinfunction "2_2") (pintype "passive"))
      (node (ref "R38") (pin "2") (pinfunction "2_2") (pintype "passive"))
      (node (ref "R53") (pin "2") (pinfunction "2_2") (pintype "passive"))
      (node (ref "R54") (pin "2") (pinfunction "2_2") (pintype "passive"))
      (node (ref "R65") (pin "2") (pinfunction "2_2") (pintype "passive"))
      (node (ref "R72") (pin "2") (pinfunction "2_2") (pintype "passive"))
      (node (ref "X1") (pin "11") (pinfunction "S_11") (pintype "passive"))
      (node (ref "X2") (pin "1") (pinfunction "S_1") (pintype "passive"))
    )
    (net (code "44") (name "GLV_RELAY") (class "Default")
      (node (ref "X1") (pin "8") (pinfunction "S_8") (pintype "passive"))
      (node (ref "X2") (pin "4") (pinfunction "S_4") (pintype "passive"))
    )
    (net (code "45") (name "GLV_SW") (class "Default")
      (node (ref "D12") (pin "C") (pinfunction "C_C") (pintype "passive"))
      (node (ref "D13") (pin "C") (pinfunction "C_C") (pintype "passive"))
      (node (ref "D14") (pin "C") (pinfunction "C_C") (pintype "passive"))
      (node (ref "D15") (pin "C") (pinfunction "C_C") (pintype "passive"))
      (node (ref "D16") (pin "C") (pinfunction "C_C") (pintype "passive"))
      (node (ref "D7") (pin "C") (pinfunction "C_C") (pintype "passive"))
      (node (ref "D8") (pin "C") (pinfunction "C_C") (pintype "passive"))
      (node (ref "D9") (pin "C") (pinfunction "C_C") (pintype "passive"))
      (node (ref "RLY10") (pin "1") (pinfunction "+_1") (pintype "passive"))
      (node (ref "RLY10") (pin "5") (pinfunction "S_5") (pintype "passive"))
      (node (ref "RLY13") (pin "1") (pinfunction "+_1") (pintype "passive"))
      (node (ref "RLY13") (pin "5") (pinfunction "S_5") (pintype "passive"))
      (node (ref "RLY14") (pin "1") (pinfunction "+_1") (pintype "passive"))
      (node (ref "RLY14") (pin "5") (pinfunction "S_5") (pintype "passive"))
      (node (ref "RLY16") (pin "1") (pinfunction "+_1") (pintype "passive"))
      (node (ref "RLY16") (pin "5") (pinfunction "S_5") (pintype "passive"))
      (node (ref "RLY4") (pin "1") (pinfunction "+_1") (pintype "passive"))
      (node (ref "RLY4") (pin "5") (pinfunction "S_5") (pintype "passive"))
      (node (ref "RLY5") (pin "1") (pinfunction "+_1") (pintype "passive"))
      (node (ref "RLY5") (pin "5") (pinfunction "S_5") (pintype "passive"))
      (node (ref "RLY6") (pin "1") (pinfunction "+_1") (pintype "passive"))
      (node (ref "RLY6") (pin "5") (pinfunction "S_5") (pintype "passive"))
      (node (ref "RLY9") (pin "1") (pinfunction "+_1") (pintype "passive"))
      (node (ref "RLY9") (pin "5") (pinfunction "S_5") (pintype "passive"))
      (node (ref "X1") (pin "9") (pinfunction "S_9") (pintype "passive"))
      (node (ref "X2") (pin "3") (pinfunction "S_3") (pintype "passive"))
    )
    (net (code "46") (name "GND") (class "Default")
      (node (ref "C1") (pin "2") (pinfunction "2_2") (pintype "passive"))
      (node (ref "C2") (pin "2") (pinfunction "2_2") (pintype "passive"))
      (node (ref "C3") (pin "2") (pinfunction "2_2") (pintype "passive"))
      (node (ref "C4") (pin "2") (pinfunction "2_2") (pintype "passive"))
      (node (ref "C5") (pin "2") (pinfunction "2_2") (pintype "passive"))
      (node (ref "D1") (pin "1") (pinfunction "A_1") (pintype "passive"))
      (node (ref "D10") (pin "1") (pinfunction "A_1") (pintype "passive"))
      (node (ref "D11") (pin "1") (pinfunction "A_1") (pintype "passive"))
      (node (ref "D12") (pin "A") (pinfunction "A_A") (pintype "passive"))
      (node (ref "D13") (pin "A") (pinfunction "A_A") (pintype "passive"))
      (node (ref "D14") (pin "A") (pinfunction "A_A") (pintype "passive"))
      (node (ref "D15") (pin "A") (pinfunction "A_A") (pintype "passive"))
      (node (ref "D16") (pin "A") (pinfunction "A_A") (pintype "passive"))
      (node (ref "D2") (pin "1") (pinfunction "A_1") (pintype "passive"))
      (node (ref "D3") (pin "1") (pinfunction "A_1") (pintype "passive"))
      (node (ref "D4") (pin "1") (pinfunction "A_1") (pintype "passive"))
      (node (ref "D5") (pin "1") (pinfunction "A_1") (pintype "passive"))
      (node (ref "D6") (pin "1") (pinfunction "A_1") (pintype "passive"))
      (node (ref "D7") (pin "A") (pinfunction "A_A") (pintype "passive"))
      (node (ref "D8") (pin "A") (pinfunction "A_A") (pintype "passive"))
      (node (ref "D9") (pin "A") (pinfunction "A_A") (pintype "passive"))
      (node (ref "LED1") (pin "C") (pinfunction "C_C") (pintype "passive"))
      (node (ref "LED2") (pin "C") (pinfunction "C_C") (pintype "passive"))
      (node (ref "Q10") (pin "2") (pinfunction "S_2") (pintype "passive"))
      (node (ref "Q15") (pin "2") (pinfunction "S_2") (pintype "passive"))
      (node (ref "Q16") (pin "2") (pinfunction "S_2") (pintype "passive"))
      (node (ref "Q20") (pin "2") (pinfunction "S_2") (pintype "passive"))
      (node (ref "Q23") (pin "2") (pinfunction "S_2") (pintype "passive"))
      (node (ref "Q3") (pin "2") (pinfunction "S_2") (pintype "passive"))
      (node (ref "Q4") (pin "2") (pinfunction "S_2") (pintype "passive"))
      (node (ref "Q9") (pin "2") (pinfunction "S_2") (pintype "passive"))
      (node (ref "R12") (pin "1") (pinfunction "1_1") (pintype "passive"))
      (node (ref "R13") (pin "1") (pinfunction "1_1") (pintype "passive"))
      (node (ref "R35") (pin "1") (pinfunction "1_1") (pintype "passive"))
      (node (ref "R36") (pin "1") (pinfunction "1_1") (pintype "passive"))
      (node (ref "R51") (pin "1") (pinfunction "1_1") (pintype "passive"))
      (node (ref "R52") (pin "1") (pinfunction "1_1") (pintype "passive"))
      (node (ref "R64") (pin "1") (pinfunction "1_1") (pintype "passive"))
      (node (ref "R71") (pin "1") (pinfunction "1_1") (pintype "passive"))
      (node (ref "RLY1") (pin "2") (pinfunction "O_2") (pintype "passive"))
      (node (ref "RLY10") (pin "2") (pinfunction "O_2") (pintype "passive"))
      (node (ref "RLY10") (pin "8") (pinfunction "-_8") (pintype "passive"))
      (node (ref "RLY11") (pin "2") (pinfunction "O_2") (pintype "passive"))
      (node (ref "RLY12") (pin "2") (pinfunction "O_2") (pintype "passive"))
      (node (ref "RLY13") (pin "2") (pinfunction "O_2") (pintype "passive"))
      (node (ref "RLY13") (pin "8") (pinfunction "-_8") (pintype "passive"))
      (node (ref "RLY14") (pin "2") (pinfunction "O_2") (pintype "passive"))
      (node (ref "RLY14") (pin "8") (pinfunction "-_8") (pintype "passive"))
      (node (ref "RLY15") (pin "2") (pinfunction "O_2") (pintype "passive"))
      (node (ref "RLY16") (pin "2") (pinfunction "O_2") (pintype "passive"))
      (node (ref "RLY16") (pin "8") (pinfunction "-_8") (pintype "passive"))
      (node (ref "RLY2") (pin "2") (pinfunction "O_2") (pintype "passive"))
      (node (ref "RLY3") (pin "2") (pinfunction "O_2") (pintype "passive"))
      (node (ref "RLY4") (pin "2") (pinfunction "O_2") (pintype "passive"))
      (node (ref "RLY4") (pin "8") (pinfunction "-_8") (pintype "passive"))
      (node (ref "RLY5") (pin "2") (pinfunction "O_2") (pintype "passive"))
      (node (ref "RLY5") (pin "8") (pinfunction "-_8") (pintype "passive"))
      (node (ref "RLY6") (pin "2") (pinfunction "O_2") (pintype "passive"))
      (node (ref "RLY6") (pin "8") (pinfunction "-_8") (pintype "passive"))
      (node (ref "RLY7") (pin "2") (pinfunction "O_2") (pintype "passive"))
      (node (ref "RLY8") (pin "2") (pinfunction "O_2") (pintype "passive"))
      (node (ref "RLY9") (pin "2") (pinfunction "O_2") (pintype "passive"))
      (node (ref "RLY9") (pin "8") (pinfunction "-_8") (pintype "passive"))
      (node (ref "U1") (pin "13") (pinfunction "G_13") (pintype "input"))
      (node (ref "U1") (pin "8") (pinfunction "GND_8") (pintype "power_in"))
      (node (ref "U2") (pin "10") (pinfunction "I1_10") (pintype "input"))
      (node (ref "U2") (pin "12") (pinfunction "I0_12") (pintype "input"))
      (node (ref "U2") (pin "13") (pinfunction "I1_13") (pintype "input"))
      (node (ref "U2") (pin "4") (pinfunction "I0_4") (pintype "input"))
      (node (ref "U2") (pin "5") (pinfunction "I1_5") (pintype "input"))
      (node (ref "U2") (pin "7") (pinfunction "GND_7") (pintype "power_in"))
      (node (ref "U2") (pin "9") (pinfunction "I0_9") (pintype "input"))
      (node (ref "U3") (pin "10") (pinfunction "GND_10") (pintype "power_in"))
      (node (ref "U4") (pin "9") (pinfunction "GND_9") (pintype "passive"))
      (node (ref "X1") (pin "2") (pinfunction "S_2") (pintype "passive"))
      (node (ref "X2") (pin "10") (pinfunction "S_10") (pintype "passive"))
      (node (ref "X3") (pin "5") (pinfunction "S_5") (pintype "passive"))
      (node (ref "X4") (pin "5") (pinfunction "S_5") (pintype "passive"))
      (node (ref "X5") (pin "5") (pinfunction "S_5") (pintype "passive"))
      (node (ref "X6") (pin "5") (pinfunction "S_5") (pintype "passive"))
      (node (ref "X7") (pin "1") (pinfunction "S_1") (pintype "passive"))
    )
    (net (code "47") (name "Net-(D1-C)") (class "Default")
      (node (ref "D1") (pin "3") (pinfunction "C_3") (pintype "passive"))
      (node (ref "Q3") (pin "1") (pinfunction "G_1") (pintype "passive"))
      (node (ref "R12") (pin "2") (pinfunction "2_2") (pintype "passive"))
      (node (ref "R3") (pin "1") (pinfunction "1_1") (pintype "passive"))
      (node (ref "R5") (pin "2") (pinfunction "2_2") (pintype "passive"))
    )
    (net (code "48") (name "Net-(D2-C)") (class "Default")
      (node (ref "D2") (pin "3") (pinfunction "C_3") (pintype "passive"))
      (node (ref "Q4") (pin "1") (pinfunction "G_1") (pintype "passive"))
      (node (ref "R13") (pin "2") (pinfunction "2_2") (pintype "passive"))
      (node (ref "R4") (pin "1") (pinfunction "1_1") (pintype "passive"))
      (node (ref "R6") (pin "2") (pinfunction "2_2") (pintype "passive"))
    )
    (net (code "49") (name "Net-(D3-C)") (class "Default")
      (node (ref "D3") (pin "3") (pinfunction "C_3") (pintype "passive"))
      (node (ref "Q9") (pin "1") (pinfunction "G_1") (pintype "passive"))
      (node (ref "R26") (pin "1") (pinfunction "1_1") (pintype "passive"))
      (node (ref "R29") (pin "2") (pinfunction "2_2") (pintype "passive"))
      (node (ref "R35") (pin "2") (pinfunction "2_2") (pintype "passive"))
    )
    (net (code "50") (name "Net-(D4-C)") (class "Default")
      (node (ref "D4") (pin "3") (pinfunction "C_3") (pintype "passive"))
      (node (ref "Q10") (pin "1") (pinfunction "G_1") (pintype "passive"))
      (node (ref "R27") (pin "1") (pinfunction "1_1") (pintype "passive"))
      (node (ref "R30") (pin "2") (pinfunction "2_2") (pintype "passive"))
      (node (ref "R36") (pin "2") (pinfunction "2_2") (pintype "passive"))
    )
    (net (code "51") (name "Net-(D5-C)") (class "Default")
      (node (ref "D5") (pin "3") (pinfunction "C_3") (pintype "passive"))
      (node (ref "Q15") (pin "1") (pinfunction "G_1") (pintype "passive"))
      (node (ref "R43") (pin "1") (pinfunction "1_1") (pintype "passive"))
      (node (ref "R45") (pin "2") (pinfunction "2_2") (pintype "passive"))
      (node (ref "R51") (pin "2") (pinfunction "2_2") (pintype "passive"))
    )
    (net (code "52") (name "Net-(D6-C)") (class "Default")
      (node (ref "D6") (pin "3") (pinfunction "C_3") (pintype "passive"))
      (node (ref "Q16") (pin "1") (pinfunction "G_1") (pintype "passive"))
      (node (ref "R44") (pin "1") (pinfunction "1_1") (pintype "passive"))
      (node (ref "R46") (pin "2") (pinfunction "2_2") (pintype "passive"))
      (node (ref "R52") (pin "2") (pinfunction "2_2") (pintype "passive"))
    )
    (net (code "53") (name "Net-(D10-C)") (class "Default")
      (node (ref "D10") (pin "3") (pinfunction "C_3") (pintype "passive"))
      (node (ref "Q20") (pin "1") (pinfunction "G_1") (pintype "passive"))
      (node (ref "R59") (pin "1") (pinfunction "1_1") (pintype "passive"))
      (node (ref "R60") (pin "2") (pinfunction "2_2") (pintype "passive"))
      (node (ref "R64") (pin "2") (pinfunction "2_2") (pintype "passive"))
    )
    (net (code "54") (name "Net-(D11-C)") (class "Default")
      (node (ref "D11") (pin "3") (pinfunction "C_3") (pintype "passive"))
      (node (ref "Q23") (pin "1") (pinfunction "G_1") (pintype "passive"))
      (node (ref "R62") (pin "1") (pinfunction "1_1") (pintype "passive"))
      (node (ref "R66") (pin "2") (pinfunction "2_2") (pintype "passive"))
      (node (ref "R71") (pin "2") (pinfunction "2_2") (pintype "passive"))
    )
    (net (code "55") (name "Net-(LED1-PadA)") (class "Default")
      (node (ref "LED1") (pin "A") (pinfunction "A_A") (pintype "passive"))
      (node (ref "R1") (pin "2") (pinfunction "2_2") (pintype "passive"))
    )
    (net (code "56") (name "Net-(LED2-PadA)") (class "Default")
      (node (ref "LED2") (pin "A") (pinfunction "A_A") (pintype "passive"))
      (node (ref "R2") (pin "1") (pinfunction "1_1") (pintype "passive"))
    )
    (net (code "57") (name "Net-(Q1-G)") (class "Default")
      (node (ref "Q1") (pin "1") (pinfunction "G_1") (pintype "passive"))
      (node (ref "R5") (pin "1") (pinfunction "1_1") (pintype "passive"))
      (node (ref "R7") (pin "2") (pinfunction "2_2") (pintype "passive"))
    )
    (net (code "58") (name "Net-(Q1-S)") (class "Default")
      (node (ref "Q1") (pin "2") (pinfunction "S_2") (pintype "passive"))
      (node (ref "R7") (pin "1") (pinfunction "1_1") (pintype "passive"))
      (node (ref "R9") (pin "2") (pinfunction "2_2") (pintype "passive"))
    )
    (net (code "59") (name "Net-(Q2-G)") (class "Default")
      (node (ref "Q2") (pin "1") (pinfunction "G_1") (pintype "passive"))
      (node (ref "R6") (pin "1") (pinfunction "1_1") (pintype "passive"))
      (node (ref "R8") (pin "2") (pinfunction "2_2") (pintype "passive"))
    )
    (net (code "60") (name "Net-(Q2-S)") (class "Default")
      (node (ref "Q2") (pin "2") (pinfunction "S_2") (pintype "passive"))
      (node (ref "R10") (pin "2") (pinfunction "2_2") (pintype "passive"))
      (node (ref "R8") (pin "1") (pinfunction "1_1") (pintype "passive"))
    )
    (net (code "61") (name "Net-(Q3-D)") (class "Default")
      (node (ref "Q3") (pin "5") (pinfunction "D_5") (pintype "passive"))
      (node (ref "Q5") (pin "1") (pinfunction "G_1") (pintype "passive"))
      (node (ref "R15") (pin "1") (pinfunction "1_1") (pintype "passive"))
      (node (ref "R18") (pin "2") (pinfunction "2_2") (pintype "passive"))
    )
    (net (code "62") (name "Net-(Q4-D)") (class "Default")
      (node (ref "Q4") (pin "5") (pinfunction "D_5") (pintype "passive"))
      (node (ref "Q6") (pin "1") (pinfunction "G_1") (pintype "passive"))
      (node (ref "R16") (pin "1") (pinfunction "1_1") (pintype "passive"))
      (node (ref "R19") (pin "2") (pinfunction "2_2") (pintype "passive"))
    )
    (net (code "63") (name "Net-(Q5-S)") (class "Default")
      (node (ref "Q5") (pin "2") (pinfunction "S_2") (pintype "passive"))
      (node (ref "R18") (pin "1") (pinfunction "1_1") (pintype "passive"))
      (node (ref "R21") (pin "2") (pinfunction "2_2") (pintype "passive"))
    )
    (net (code "64") (name "Net-(Q6-S)") (class "Default")
      (node (ref "Q6") (pin "2") (pinfunction "S_2") (pintype "passive"))
      (node (ref "R19") (pin "1") (pinfunction "1_1") (pintype "passive"))
      (node (ref "R22") (pin "2") (pinfunction "2_2") (pintype "passive"))
    )
    (net (code "65") (name "Net-(Q7-G)") (class "Default")
      (node (ref "Q7") (pin "1") (pinfunction "G_1") (pintype "passive"))
      (node (ref "R29") (pin "1") (pinfunction "1_1") (pintype "passive"))
      (node (ref "R31") (pin "2") (pinfunction "2_2") (pintype "passive"))
    )
    (net (code "66") (name "Net-(Q7-S)") (class "Default")
      (node (ref "Q7") (pin "2") (pinfunction "S_2") (pintype "passive"))
      (node (ref "R31") (pin "1") (pinfunction "1_1") (pintype "passive"))
      (node (ref "R33") (pin "2") (pinfunction "2_2") (pintype "passive"))
    )
    (net (code "67") (name "Net-(Q8-G)") (class "Default")
      (node (ref "Q8") (pin "1") (pinfunction "G_1") (pintype "passive"))
      (node (ref "R30") (pin "1") (pinfunction "1_1") (pintype "passive"))
      (node (ref "R32") (pin "2") (pinfunction "2_2") (pintype "passive"))
    )
    (net (code "68") (name "Net-(Q8-S)") (class "Default")
      (node (ref "Q8") (pin "2") (pinfunction "S_2") (pintype "passive"))
      (node (ref "R32") (pin "1") (pinfunction "1_1") (pintype "passive"))
      (node (ref "R34") (pin "2") (pinfunction "2_2") (pintype "passive"))
    )
    (net (code "69") (name "Net-(Q10-D)") (class "Default")
      (node (ref "Q10") (pin "5") (pinfunction "D_5") (pintype "passive"))
      (node (ref "Q12") (pin "1") (pinfunction "G_1") (pintype "passive"))
      (node (ref "R38") (pin "1") (pinfunction "1_1") (pintype "passive"))
      (node (ref "R40") (pin "2") (pinfunction "2_2") (pintype "passive"))
    )
    (net (code "70") (name "Net-(Q11-G)") (class "Default")
      (node (ref "Q11") (pin "1") (pinfunction "G_1") (pintype "passive"))
      (node (ref "Q9") (pin "5") (pinfunction "D_5") (pintype "passive"))
      (node (ref "R37") (pin "1") (pinfunction "1_1") (pintype "passive"))
      (node (ref "R39") (pin "2") (pinfunction "2_2") (pintype "passive"))
    )
    (net (code "71") (name "Net-(Q11-S)") (class "Default")
      (node (ref "Q11") (pin "2") (pinfunction "S_2") (pintype "passive"))
      (node (ref "R39") (pin "1") (pinfunction "1_1") (pintype "passive"))
      (node (ref "R41") (pin "2") (pinfunction "2_2") (pintype "passive"))
    )
    (net (code "72") (name "Net-(Q12-S)") (class "Default")
      (node (ref "Q12") (pin "2") (pinfunction "S_2") (pintype "passive"))
      (node (ref "R40") (pin "1") (pinfunction "1_1") (pintype "passive"))
      (node (ref "R42") (pin "2") (pinfunction "2_2") (pintype "passive"))
    )
    (net (code "73") (name "Net-(Q13-G)") (class "Default")
      (node (ref "Q13") (pin "1") (pinfunction "G_1") (pintype "passive"))
      (node (ref "R45") (pin "1") (pinfunction "1_1") (pintype "passive"))
      (node (ref "R47") (pin "2") (pinfunction "2_2") (pintype "passive"))
    )
    (net (code "74") (name "Net-(Q13-S)") (class "Default")
      (node (ref "Q13") (pin "2") (pinfunction "S_2") (pintype "passive"))
      (node (ref "R47") (pin "1") (pinfunction "1_1") (pintype "passive"))
      (node (ref "R49") (pin "2") (pinfunction "2_2") (pintype "passive"))
    )
    (net (code "75") (name "Net-(Q14-G)") (class "Default")
      (node (ref "Q14") (pin "1") (pinfunction "G_1") (pintype "passive"))
      (node (ref "R46") (pin "1") (pinfunction "1_1") (pintype "passive"))
      (node (ref "R48") (pin "2") (pinfunction "2_2") (pintype "passive"))
    )
    (net (code "76") (name "Net-(Q14-S)") (class "Default")
      (node (ref "Q14") (pin "2") (pinfunction "S_2") (pintype "passive"))
      (node (ref "R48") (pin "1") (pinfunction "1_1") (pintype "passive"))
      (node (ref "R50") (pin "2") (pinfunction "2_2") (pintype "passive"))
    )
    (net (code "77") (name "Net-(Q15-D)") (class "Default")
      (node (ref "Q15") (pin "5") (pinfunction "D_5") (pintype "passive"))
      (node (ref "Q17") (pin "1") (pinfunction "G_1") (pintype "passive"))
      (node (ref "R53") (pin "1") (pinfunction "1_1") (pintype "passive"))
      (node (ref "R55") (pin "2") (pinfunction "2_2") (pintype "passive"))
    )
    (net (code "78") (name "Net-(Q16-D)") (class "Default")
      (node (ref "Q16") (pin "5") (pinfunction "D_5") (pintype "passive"))
      (node (ref "Q18") (pin "1") (pinfunction "G_1") (pintype "passive"))
      (node (ref "R54") (pin "1") (pinfunction "1_1") (pintype "passive"))
      (node (ref "R56") (pin "2") (pinfunction "2_2") (pintype "passive"))
    )
    (net (code "79") (name "Net-(Q17-S)") (class "Default")
      (node (ref "Q17") (pin "2") (pinfunction "S_2") (pintype "passive"))
      (node (ref "R55") (pin "1") (pinfunction "1_1") (pintype "passive"))
      (node (ref "R57") (pin "2") (pinfunction "2_2") (pintype "passive"))
    )
    (net (code "80") (name "Net-(Q18-S)") (class "Default")
      (node (ref "Q18") (pin "2") (pinfunction "S_2") (pintype "passive"))
      (node (ref "R56") (pin "1") (pinfunction "1_1") (pintype "passive"))
      (node (ref "R58") (pin "2") (pinfunction "2_2") (pintype "passive"))
    )
    (net (code "81") (name "Net-(Q19-G)") (class "Default")
      (node (ref "Q19") (pin "1") (pinfunction "G_1") (pintype "passive"))
      (node (ref "R60") (pin "1") (pinfunction "1_1") (pintype "passive"))
      (node (ref "R61") (pin "2") (pinfunction "2_2") (pintype "passive"))
    )
    (net (code "82") (name "Net-(Q19-S)") (class "Default")
      (node (ref "Q19") (pin "2") (pinfunction "S_2") (pintype "passive"))
      (node (ref "R61") (pin "1") (pinfunction "1_1") (pintype "passive"))
      (node (ref "R63") (pin "2") (pinfunction "2_2") (pintype "passive"))
    )
    (net (code "83") (name "Net-(Q20-D)") (class "Default")
      (node (ref "Q20") (pin "5") (pinfunction "D_5") (pintype "passive"))
      (node (ref "Q22") (pin "1") (pinfunction "G_1") (pintype "passive"))
      (node (ref "R65") (pin "1") (pinfunction "1_1") (pintype "passive"))
      (node (ref "R68") (pin "2") (pinfunction "2_2") (pintype "passive"))
    )
    (net (code "84") (name "Net-(Q21-G)") (class "Default")
      (node (ref "Q21") (pin "1") (pinfunction "G_1") (pintype "passive"))
      (node (ref "R66") (pin "1") (pinfunction "1_1") (pintype "passive"))
      (node (ref "R67") (pin "2") (pinfunction "2_2") (pintype "passive"))
    )
    (net (code "85") (name "Net-(Q21-S)") (class "Default")
      (node (ref "Q21") (pin "2") (pinfunction "S_2") (pintype "passive"))
      (node (ref "R67") (pin "1") (pinfunction "1_1") (pintype "passive"))
      (node (ref "R69") (pin "2") (pinfunction "2_2") (pintype "passive"))
    )
    (net (code "86") (name "Net-(Q22-S)") (class "Default")
      (node (ref "Q22") (pin "2") (pinfunction "S_2") (pintype "passive"))
      (node (ref "R68") (pin "1") (pinfunction "1_1") (pintype "passive"))
      (node (ref "R70") (pin "2") (pinfunction "2_2") (pintype "passive"))
    )
    (net (code "87") (name "Net-(Q23-D)") (class "Default")
      (node (ref "Q23") (pin "5") (pinfunction "D_5") (pintype "passive"))
      (node (ref "Q24") (pin "1") (pinfunction "G_1") (pintype "passive"))
      (node (ref "R72") (pin "1") (pinfunction "1_1") (pintype "passive"))
      (node (ref "R73") (pin "2") (pinfunction "2_2") (pintype "passive"))
    )
    (net (code "88") (name "Net-(Q24-S)") (class "Default")
      (node (ref "Q24") (pin "2") (pinfunction "S_2") (pintype "passive"))
      (node (ref "R73") (pin "1") (pinfunction "1_1") (pintype "passive"))
      (node (ref "R74") (pin "2") (pinfunction "2_2") (pintype "passive"))
    )
    (net (code "89") (name "Net-(RLY1A--)") (class "Default")
      (node (ref "RLY1") (pin "8") (pinfunction "-_8") (pintype "passive"))
      (node (ref "U4") (pin "18") (pinfunction "1C_18") (pintype "output"))
    )
    (net (code "90") (name "Net-(RLY1B-S)") (class "Default")
      (node (ref "RLY1") (pin "3") (pinfunction "P_3") (pintype "passive"))
      (node (ref "RLY1") (pin "5") (pinfunction "S_5") (pintype "passive"))
      (node (ref "RLY4") (pin "7") (pinfunction "O_7") (pintype "passive"))
    )
    (net (code "91") (name "Net-(RLY2A--)") (class "Default")
      (node (ref "RLY2") (pin "8") (pinfunction "-_8") (pintype "passive"))
      (node (ref "U4") (pin "16") (pinfunction "3C_16") (pintype "output"))
    )
    (net (code "92") (name "Net-(RLY2B-S)") (class "Default")
      (node (ref "RLY2") (pin "3") (pinfunction "P_3") (pintype "passive"))
      (node (ref "RLY2") (pin "5") (pinfunction "S_5") (pintype "passive"))
      (node (ref "RLY5") (pin "7") (pinfunction "O_7") (pintype "passive"))
    )
    (net (code "93") (name "Net-(RLY3A--)") (class "Default")
      (node (ref "RLY3") (pin "8") (pinfunction "-_8") (pintype "passive"))
      (node (ref "U4") (pin "14") (pinfunction "5C_14") (pintype "output"))
    )
    (net (code "94") (name "Net-(RLY3B-S)") (class "Default")
      (node (ref "RLY3") (pin "3") (pinfunction "P_3") (pintype "passive"))
      (node (ref "RLY3") (pin "5") (pinfunction "S_5") (pintype "passive"))
      (node (ref "RLY6") (pin "7") (pinfunction "O_7") (pintype "passive"))
    )
    (net (code "95") (name "Net-(RLY7A--)") (class "Default")
      (node (ref "RLY7") (pin "8") (pinfunction "-_8") (pintype "passive"))
      (node (ref "U4") (pin "17") (pinfunction "2C_17") (pintype "output"))
    )
    (net (code "96") (name "Net-(RLY7B-S)") (class "Default")
      (node (ref "RLY7") (pin "3") (pinfunction "P_3") (pintype "passive"))
      (node (ref "RLY7") (pin "5") (pinfunction "S_5") (pintype "passive"))
      (node (ref "RLY9") (pin "7") (pinfunction "O_7") (pintype "passive"))
    )
    (net (code "97") (name "Net-(RLY8A--)") (class "Default")
      (node (ref "RLY8") (pin "8") (pinfunction "-_8") (pintype "passive"))
      (node (ref "U4") (pin "15") (pinfunction "4C_15") (pintype "output"))
    )
    (net (code "98") (name "Net-(RLY10B-O)") (class "Default")
      (node (ref "RLY10") (pin "7") (pinfunction "O_7") (pintype "passive"))
      (node (ref "RLY8") (pin "3") (pinfunction "P_3") (pintype "passive"))
      (node (ref "RLY8") (pin "5") (pinfunction "S_5") (pintype "passive"))
    )
    (net (code "99") (name "Net-(RLY11A--)") (class "Default")
      (node (ref "RLY11") (pin "8") (pinfunction "-_8") (pintype "passive"))
      (node (ref "U4") (pin "13") (pinfunction "6C_13") (pintype "output"))
    )
    (net (code "100") (name "Net-(RLY11B-S)") (class "Default")
      (node (ref "RLY11") (pin "3") (pinfunction "P_3") (pintype "passive"))
      (node (ref "RLY11") (pin "5") (pinfunction "S_5") (pintype "passive"))
      (node (ref "RLY13") (pin "7") (pinfunction "O_7") (pintype "passive"))
    )
    (net (code "101") (name "Net-(RLY12A--)") (class "Default")
      (node (ref "RLY12") (pin "8") (pinfunction "-_8") (pintype "passive"))
      (node (ref "U4") (pin "11") (pinfunction "8C_11") (pintype "output"))
    )
    (net (code "102") (name "Net-(RLY12B-S)") (class "Default")
      (node (ref "RLY12") (pin "3") (pinfunction "P_3") (pintype "passive"))
      (node (ref "RLY12") (pin "5") (pinfunction "S_5") (pintype "passive"))
      (node (ref "RLY14") (pin "7") (pinfunction "O_7") (pintype "passive"))
    )
    (net (code "103") (name "Net-(RLY15A--)") (class "Default")
      (node (ref "RLY15") (pin "8") (pinfunction "-_8") (pintype "passive"))
      (node (ref "U4") (pin "12") (pinfunction "7C_12") (pintype "output"))
    )
    (net (code "104") (name "Net-(RLY15B-S)") (class "Default")
      (node (ref "RLY15") (pin "3") (pinfunction "P_3") (pintype "passive"))
      (node (ref "RLY15") (pin "5") (pinfunction "S_5") (pintype "passive"))
      (node (ref "RLY16") (pin "7") (pinfunction "O_7") (pintype "passive"))
    )
    (net (code "105") (name "Net-(U1-QA)") (class "Default")
      (node (ref "R28") (pin "2") (pinfunction "2_2") (pintype "passive"))
      (node (ref "U1") (pin "15") (pinfunction "QA_15") (pintype "tri_state"))
      (node (ref "U3") (pin "2") (pinfunction "A1_2") (pintype "bidirectional"))
    )
    (net (code "106") (name "Net-(U1-QB)") (class "Default")
      (node (ref "R25") (pin "2") (pinfunction "2_2") (pintype "passive"))
      (node (ref "U1") (pin "1") (pinfunction "QB_1") (pintype "tri_state"))
      (node (ref "U3") (pin "3") (pinfunction "A2_3") (pintype "bidirectional"))
    )
    (net (code "107") (name "Net-(U1-QC)") (class "Default")
      (node (ref "R24") (pin "2") (pinfunction "2_2") (pintype "passive"))
      (node (ref "U1") (pin "2") (pinfunction "QC_2") (pintype "tri_state"))
      (node (ref "U3") (pin "4") (pinfunction "A3_4") (pintype "bidirectional"))
    )
    (net (code "108") (name "Net-(U1-QD)") (class "Default")
      (node (ref "R23") (pin "2") (pinfunction "2_2") (pintype "passive"))
      (node (ref "U1") (pin "3") (pinfunction "QD_3") (pintype "tri_state"))
      (node (ref "U3") (pin "5") (pinfunction "A4_5") (pintype "bidirectional"))
    )
    (net (code "109") (name "Net-(U1-QE)") (class "Default")
      (node (ref "R20") (pin "2") (pinfunction "2_2") (pintype "passive"))
      (node (ref "U1") (pin "4") (pinfunction "QE_4") (pintype "tri_state"))
      (node (ref "U3") (pin "6") (pinfunction "A5_6") (pintype "bidirectional"))
    )
    (net (code "110") (name "Net-(U1-QF)") (class "Default")
      (node (ref "R17") (pin "2") (pinfunction "2_2") (pintype "passive"))
      (node (ref "U1") (pin "5") (pinfunction "QF_5") (pintype "tri_state"))
      (node (ref "U3") (pin "7") (pinfunction "A6_7") (pintype "bidirectional"))
    )
    (net (code "111") (name "Net-(U1-QG)") (class "Default")
      (node (ref "R14") (pin "2") (pinfunction "2_2") (pintype "passive"))
      (node (ref "U1") (pin "6") (pinfunction "QG_6") (pintype "tri_state"))
      (node (ref "U3") (pin "8") (pinfunction "A7_8") (pintype "bidirectional"))
    )
    (net (code "112") (name "Net-(U1-QH)") (class "Default")
      (node (ref "R11") (pin "2") (pinfunction "2_2") (pintype "passive"))
      (node (ref "U1") (pin "7") (pinfunction "QH_7") (pintype "tri_state"))
      (node (ref "U3") (pin "9") (pinfunction "A8_9") (pintype "bidirectional"))
    )
    (net (code "113") (name "Net-(U2A-O)") (class "Default")
      (node (ref "U2") (pin "3") (pinfunction "O_3") (pintype "output"))
      (node (ref "U3") (pin "19") (pinfunction "OE_19") (pintype "input"))
    )
    (net (code "114") (name "Net-(U3-B1)") (class "Default")
      (node (ref "U3") (pin "18") (pinfunction "B1_18") (pintype "bidirectional"))
      (node (ref "U4") (pin "1") (pinfunction "1B_1") (pintype "input"))
    )
    (net (code "115") (name "Net-(U3-B2)") (class "Default")
      (node (ref "U3") (pin "17") (pinfunction "B2_17") (pintype "bidirectional"))
      (node (ref "U4") (pin "2") (pinfunction "2B_2") (pintype "input"))
    )
    (net (code "116") (name "Net-(U3-B3)") (class "Default")
      (node (ref "U3") (pin "16") (pinfunction "B3_16") (pintype "bidirectional"))
      (node (ref "U4") (pin "3") (pinfunction "3B_3") (pintype "input"))
    )
    (net (code "117") (name "Net-(U3-B4)") (class "Default")
      (node (ref "U3") (pin "15") (pinfunction "B4_15") (pintype "bidirectional"))
      (node (ref "U4") (pin "4") (pinfunction "4B_4") (pintype "input"))
    )
    (net (code "118") (name "Net-(U3-B5)") (class "Default")
      (node (ref "U3") (pin "14") (pinfunction "B5_14") (pintype "bidirectional"))
      (node (ref "U4") (pin "5") (pinfunction "5B_5") (pintype "input"))
    )
    (net (code "119") (name "Net-(U3-B6)") (class "Default")
      (node (ref "U3") (pin "13") (pinfunction "B6_13") (pintype "bidirectional"))
      (node (ref "U4") (pin "6") (pinfunction "6B_6") (pintype "input"))
    )
    (net (code "120") (name "Net-(U3-B7)") (class "Default")
      (node (ref "U3") (pin "12") (pinfunction "B7_12") (pintype "bidirectional"))
      (node (ref "U4") (pin "7") (pinfunction "7B_7") (pintype "input"))
    )
    (net (code "121") (name "Net-(U3-B8)") (class "Default")
      (node (ref "U3") (pin "11") (pinfunction "B8_11") (pintype "bidirectional"))
      (node (ref "U4") (pin "8") (pinfunction "8B_8") (pintype "input"))
    )
    (net (code "122") (name "Net-(X7B-S)") (class "Default")
      (node (ref "R11") (pin "1") (pinfunction "1_1") (pintype "passive"))
      (node (ref "X7") (pin "2") (pinfunction "S_2") (pintype "passive"))
    )
    (net (code "123") (name "Net-(X7C-S)") (class "Default")
      (node (ref "R14") (pin "1") (pinfunction "1_1") (pintype "passive"))
      (node (ref "X7") (pin "3") (pinfunction "S_3") (pintype "passive"))
    )
    (net (code "124") (name "Net-(X7D-S)") (class "Default")
      (node (ref "R17") (pin "1") (pinfunction "1_1") (pintype "passive"))
      (node (ref "X7") (pin "4") (pinfunction "S_4") (pintype "passive"))
    )
    (net (code "125") (name "Net-(X7E-S)") (class "Default")
      (node (ref "R20") (pin "1") (pinfunction "1_1") (pintype "passive"))
      (node (ref "X7") (pin "5") (pinfunction "S_5") (pintype "passive"))
    )
    (net (code "126") (name "Net-(X7F-S)") (class "Default")
      (node (ref "R23") (pin "1") (pinfunction "1_1") (pintype "passive"))
      (node (ref "X7") (pin "6") (pinfunction "S_6") (pintype "passive"))
    )
    (net (code "127") (name "Net-(X7G-S)") (class "Default")
      (node (ref "R24") (pin "1") (pinfunction "1_1") (pintype "passive"))
      (node (ref "X7") (pin "7") (pinfunction "S_7") (pintype "passive"))
    )
    (net (code "128") (name "Net-(X7H-S)") (class "Default")
      (node (ref "R25") (pin "1") (pinfunction "1_1") (pintype "passive"))
      (node (ref "X7") (pin "8") (pinfunction "S_8") (pintype "passive"))
    )
    (net (code "129") (name "Net-(X7I-S)") (class "Default")
      (node (ref "R28") (pin "1") (pinfunction "1_1") (pintype "passive"))
      (node (ref "X7") (pin "9") (pinfunction "S_9") (pintype "passive"))
    )
    (net (code "130") (name "QN_ALT") (class "Default")
      (node (ref "U1") (pin "9") (pinfunction "QH*_9") (pintype "tri_state"))
      (node (ref "X2") (pin "9") (pinfunction "S_9") (pintype "passive"))
    )
    (net (code "131") (name "RCLK") (class "Default")
      (node (ref "U1") (pin "12") (pinfunction "RCLK_12") (pintype "input"))
      (node (ref "X1") (pin "6") (pinfunction "S_6") (pintype "passive"))
      (node (ref "X2") (pin "6") (pinfunction "S_6") (pintype "passive"))
    )
    (net (code "132") (name "SER") (class "Default")
      (node (ref "U1") (pin "14") (pinfunction "SER_14") (pintype "input"))
      (node (ref "X1") (pin "3") (pinfunction "S_3") (pintype "passive"))
    )
    (net (code "133") (name "SRCLK") (class "Default")
      (node (ref "U1") (pin "11") (pinfunction "SRCLK_11") (pintype "input"))
      (node (ref "U2") (pin "1") (pinfunction "I0_1") (pintype "input"))
      (node (ref "U2") (pin "2") (pinfunction "I1_2") (pintype "input"))
      (node (ref "X1") (pin "4") (pinfunction "S_4") (pintype "passive"))
      (node (ref "X2") (pin "8") (pinfunction "S_8") (pintype "passive"))
    )
    (net (code "134") (name "SRCLR") (class "Default")
      (node (ref "U1") (pin "10") (pinfunction "SCLR_10") (pintype "input"))
      (node (ref "X1") (pin "5") (pinfunction "S_5") (pintype "passive"))
      (node (ref "X2") (pin "7") (pinfunction "S_7") (pintype "passive"))
    )
    (net (code "135") (name "VDD") (class "Default")
      (node (ref "C1") (pin "1") (pinfunction "1_1") (pintype "passive"))
      (node (ref "C2") (pin "1") (pinfunction "1_1") (pintype "passive"))
      (node (ref "C3") (pin "1") (pinfunction "1_1") (pintype "passive"))
      (node (ref "C4") (pin "1") (pinfunction "1_1") (pintype "passive"))
      (node (ref "C5") (pin "1") (pinfunction "1_1") (pintype "passive"))
      (node (ref "R1") (pin "1") (pinfunction "1_1") (pintype "passive"))
      (node (ref "R2") (pin "2") (pinfunction "2_2") (pintype "passive"))
      (node (ref "U1") (pin "16") (pinfunction "VCC_16") (pintype "power_in"))
      (node (ref "U2") (pin "14") (pinfunction "VCC_14") (pintype "power_in"))
      (node (ref "U3") (pin "1") (pinfunction "DIR_1") (pintype "input"))
      (node (ref "U3") (pin "20") (pinfunction "VCC_20") (pintype "power_in"))
      (node (ref "X1") (pin "1") (pinfunction "S_1") (pintype "passive"))
      (node (ref "X2") (pin "11") (pinfunction "S_11") (pintype "passive"))
    )
    (net (code "136") (name "unconnected-(RLY1B-O-Pad7)") (class "Default")
      (node (ref "RLY1") (pin "7") (pinfunction "O_7") (pintype "passive"))
    )
    (net (code "137") (name "unconnected-(RLY1C-S-Pad4)") (class "Default")
      (node (ref "RLY1") (pin "4") (pinfunction "S_4") (pintype "passive"))
    )
    (net (code "138") (name "unconnected-(RLY2B-O-Pad7)") (class "Default")
      (node (ref "RLY2") (pin "7") (pinfunction "O_7") (pintype "passive"))
    )
    (net (code "139") (name "unconnected-(RLY2C-S-Pad4)") (class "Default")
      (node (ref "RLY2") (pin "4") (pinfunction "S_4") (pintype "passive"))
    )
    (net (code "140") (name "unconnected-(RLY3B-O-Pad7)") (class "Default")
      (node (ref "RLY3") (pin "7") (pinfunction "O_7") (pintype "passive"))
    )
    (net (code "141") (name "unconnected-(RLY3C-S-Pad4)") (class "Default")
      (node (ref "RLY3") (pin "4") (pinfunction "S_4") (pintype "passive"))
    )
    (net (code "142") (name "unconnected-(RLY7B-O-Pad7)") (class "Default")
      (node (ref "RLY7") (pin "7") (pinfunction "O_7") (pintype "passive"))
    )
    (net (code "143") (name "unconnected-(RLY7C-S-Pad4)") (class "Default")
      (node (ref "RLY7") (pin "4") (pinfunction "S_4") (pintype "passive"))
    )
    (net (code "144") (name "unconnected-(RLY8B-O-Pad7)") (class "Default")
      (node (ref "RLY8") (pin "7") (pinfunction "O_7") (pintype "passive"))
    )
    (net (code "145") (name "unconnected-(RLY8C-S-Pad4)") (class "Default")
      (node (ref "RLY8") (pin "4") (pinfunction "S_4") (pintype "passive"))
    )
    (net (code "146") (name "unconnected-(RLY11B-O-Pad7)") (class "Default")
      (node (ref "RLY11") (pin "7") (pinfunction "O_7") (pintype "passive"))
    )
    (net (code "147") (name "unconnected-(RLY11C-S-Pad4)") (class "Default")
      (node (ref "RLY11") (pin "4") (pinfunction "S_4") (pintype "passive"))
    )
    (net (code "148") (name "unconnected-(RLY12B-O-Pad7)") (class "Default")
      (node (ref "RLY12") (pin "7") (pinfunction "O_7") (pintype "passive"))
    )
    (net (code "149") (name "unconnected-(RLY12C-S-Pad4)") (class "Default")
      (node (ref "RLY12") (pin "4") (pinfunction "S_4") (pintype "passive"))
    )
    (net (code "150") (name "unconnected-(RLY15B-O-Pad7)") (class "Default")
      (node (ref "RLY15") (pin "7") (pinfunction "O_7") (pintype "passive"))
    )
    (net (code "151") (name "unconnected-(RLY15C-S-Pad4)") (class "Default")
      (node (ref "RLY15") (pin "4") (pinfunction "S_4") (pintype "passive"))
    )
    (net (code "152") (name "unconnected-(U2B-O-Pad6)") (class "Default")
      (node (ref "U2") (pin "6") (pinfunction "O_6") (pintype "output"))
    )
    (net (code "153") (name "unconnected-(U2C-O-Pad8)") (class "Default")
      (node (ref "U2") (pin "8") (pinfunction "O_8") (pintype "output"))
    )
    (net (code "154") (name "unconnected-(U2D-O-Pad11)") (class "Default")
      (node (ref "U2") (pin "11") (pinfunction "O_11") (pintype "output"))
    )
  )
)
